# Espressylu-0_6.net
KiCad netlist of a schematic drawn in EAGLE
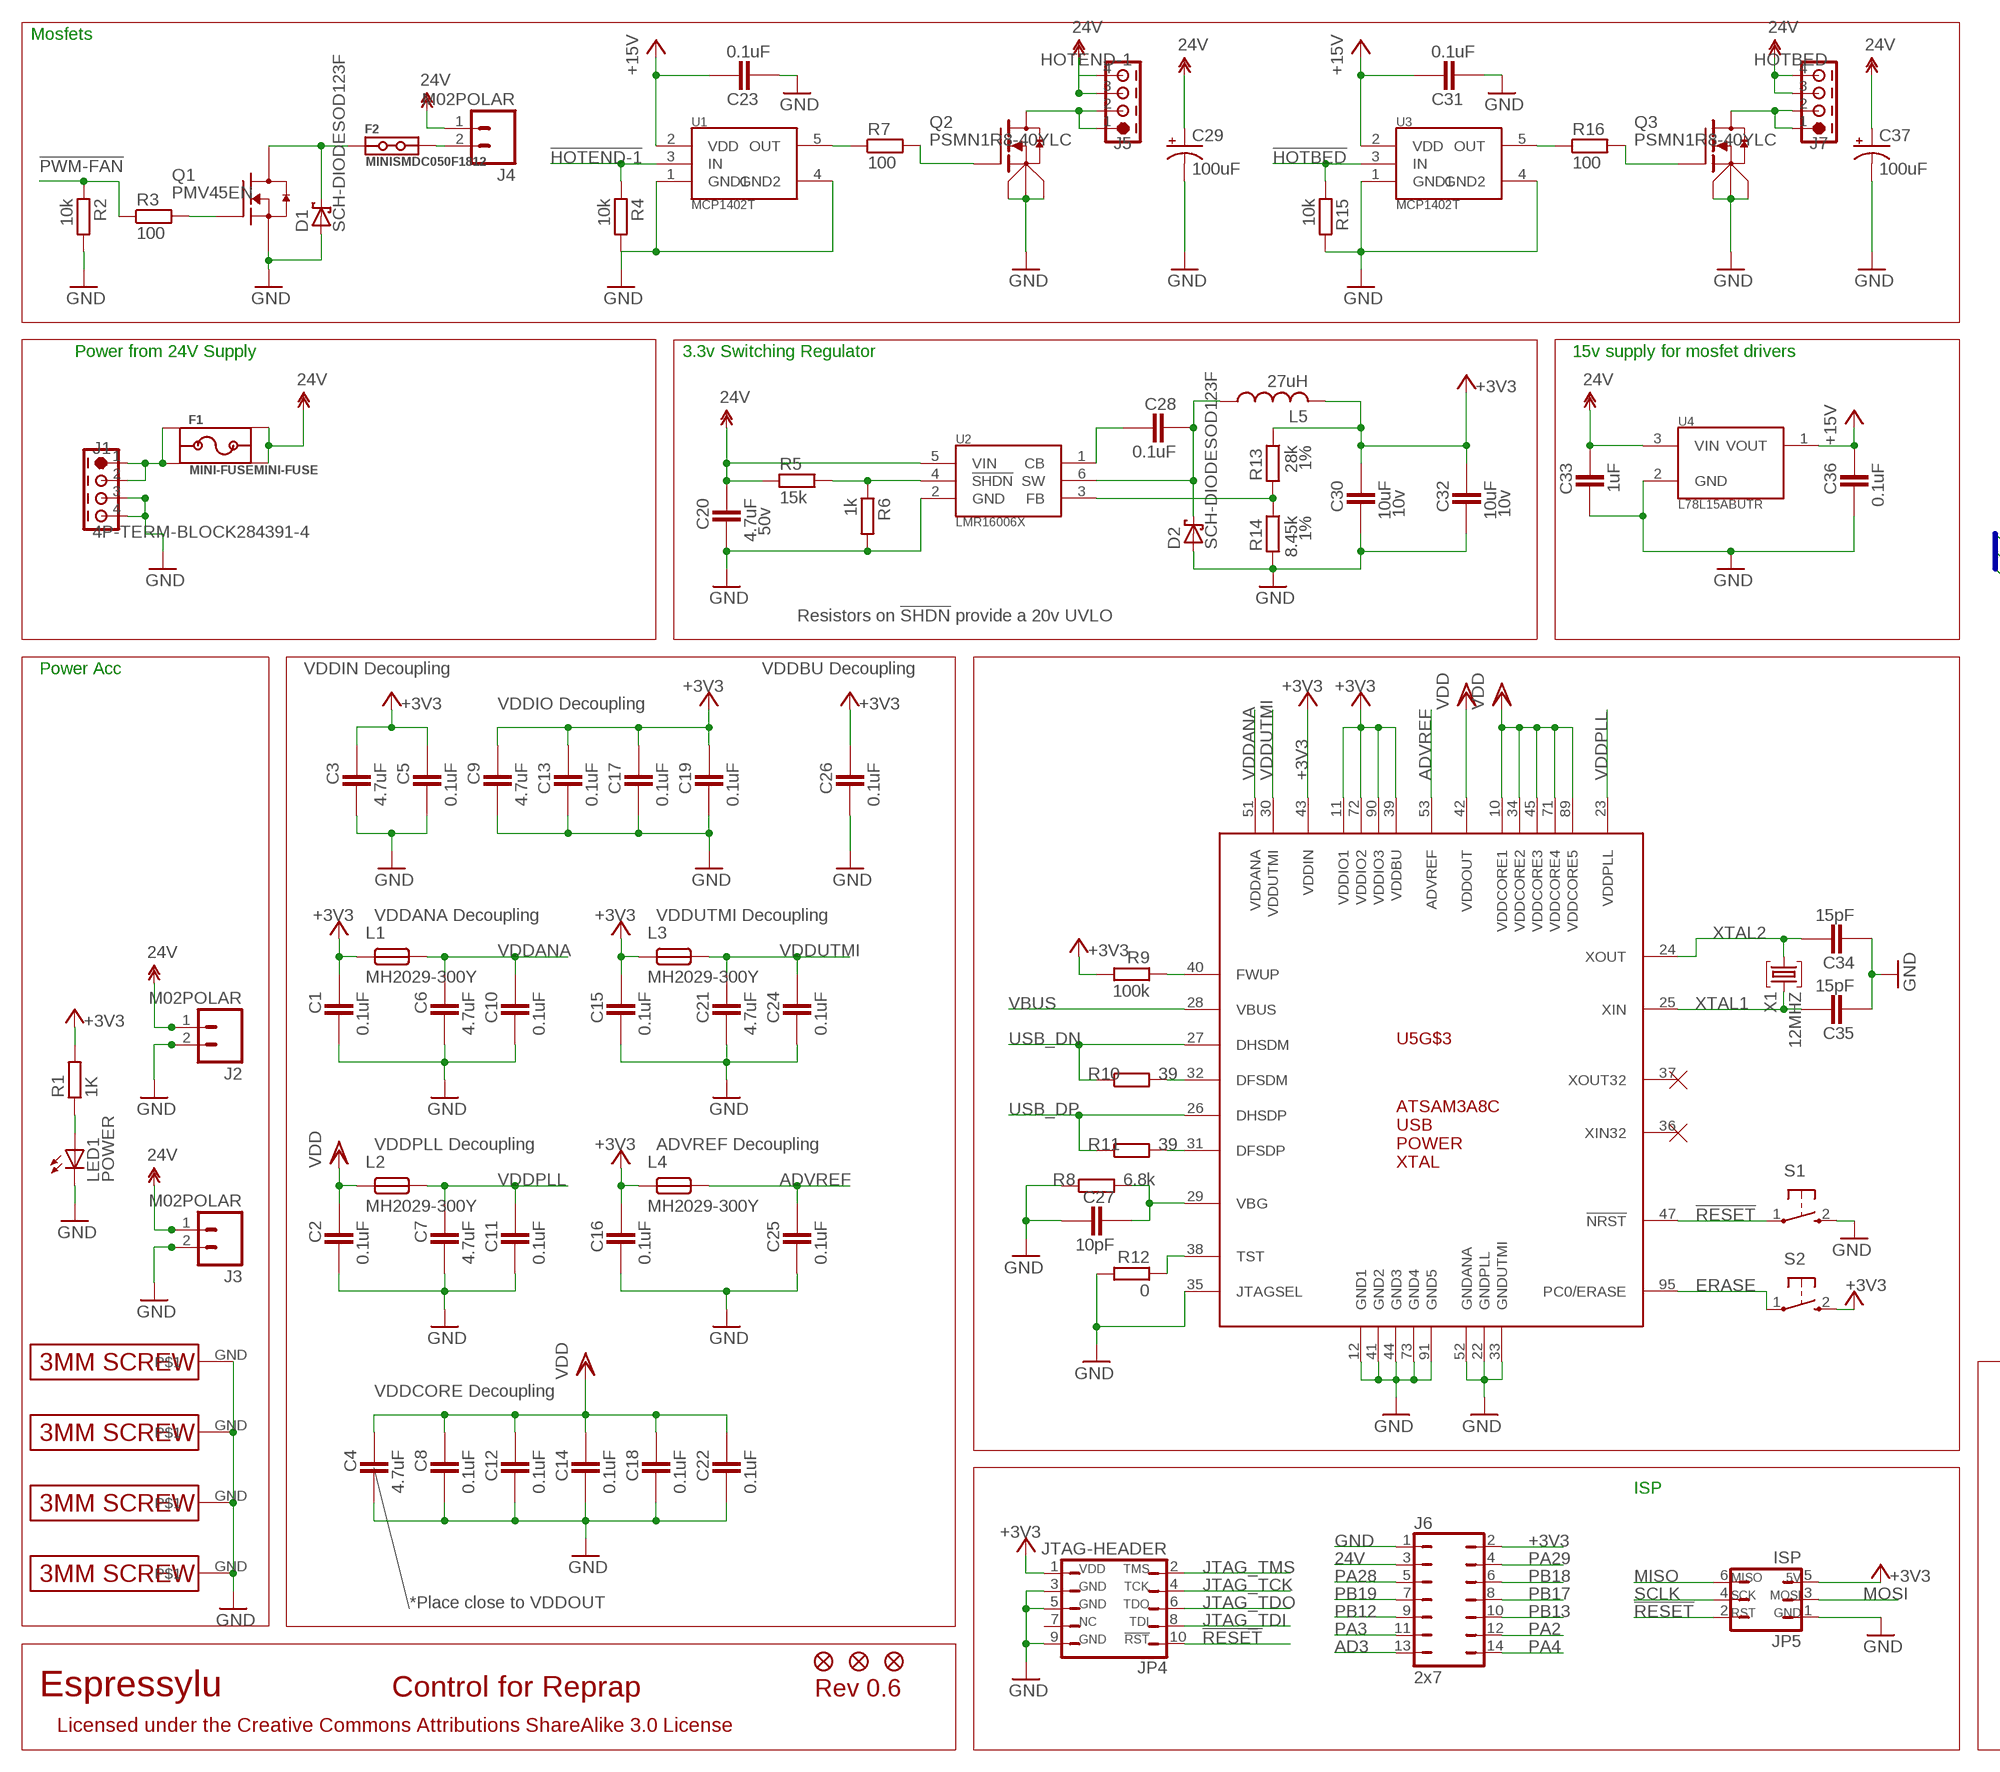
[diagram p0: schematic, sheet 1, part 1 of 2]
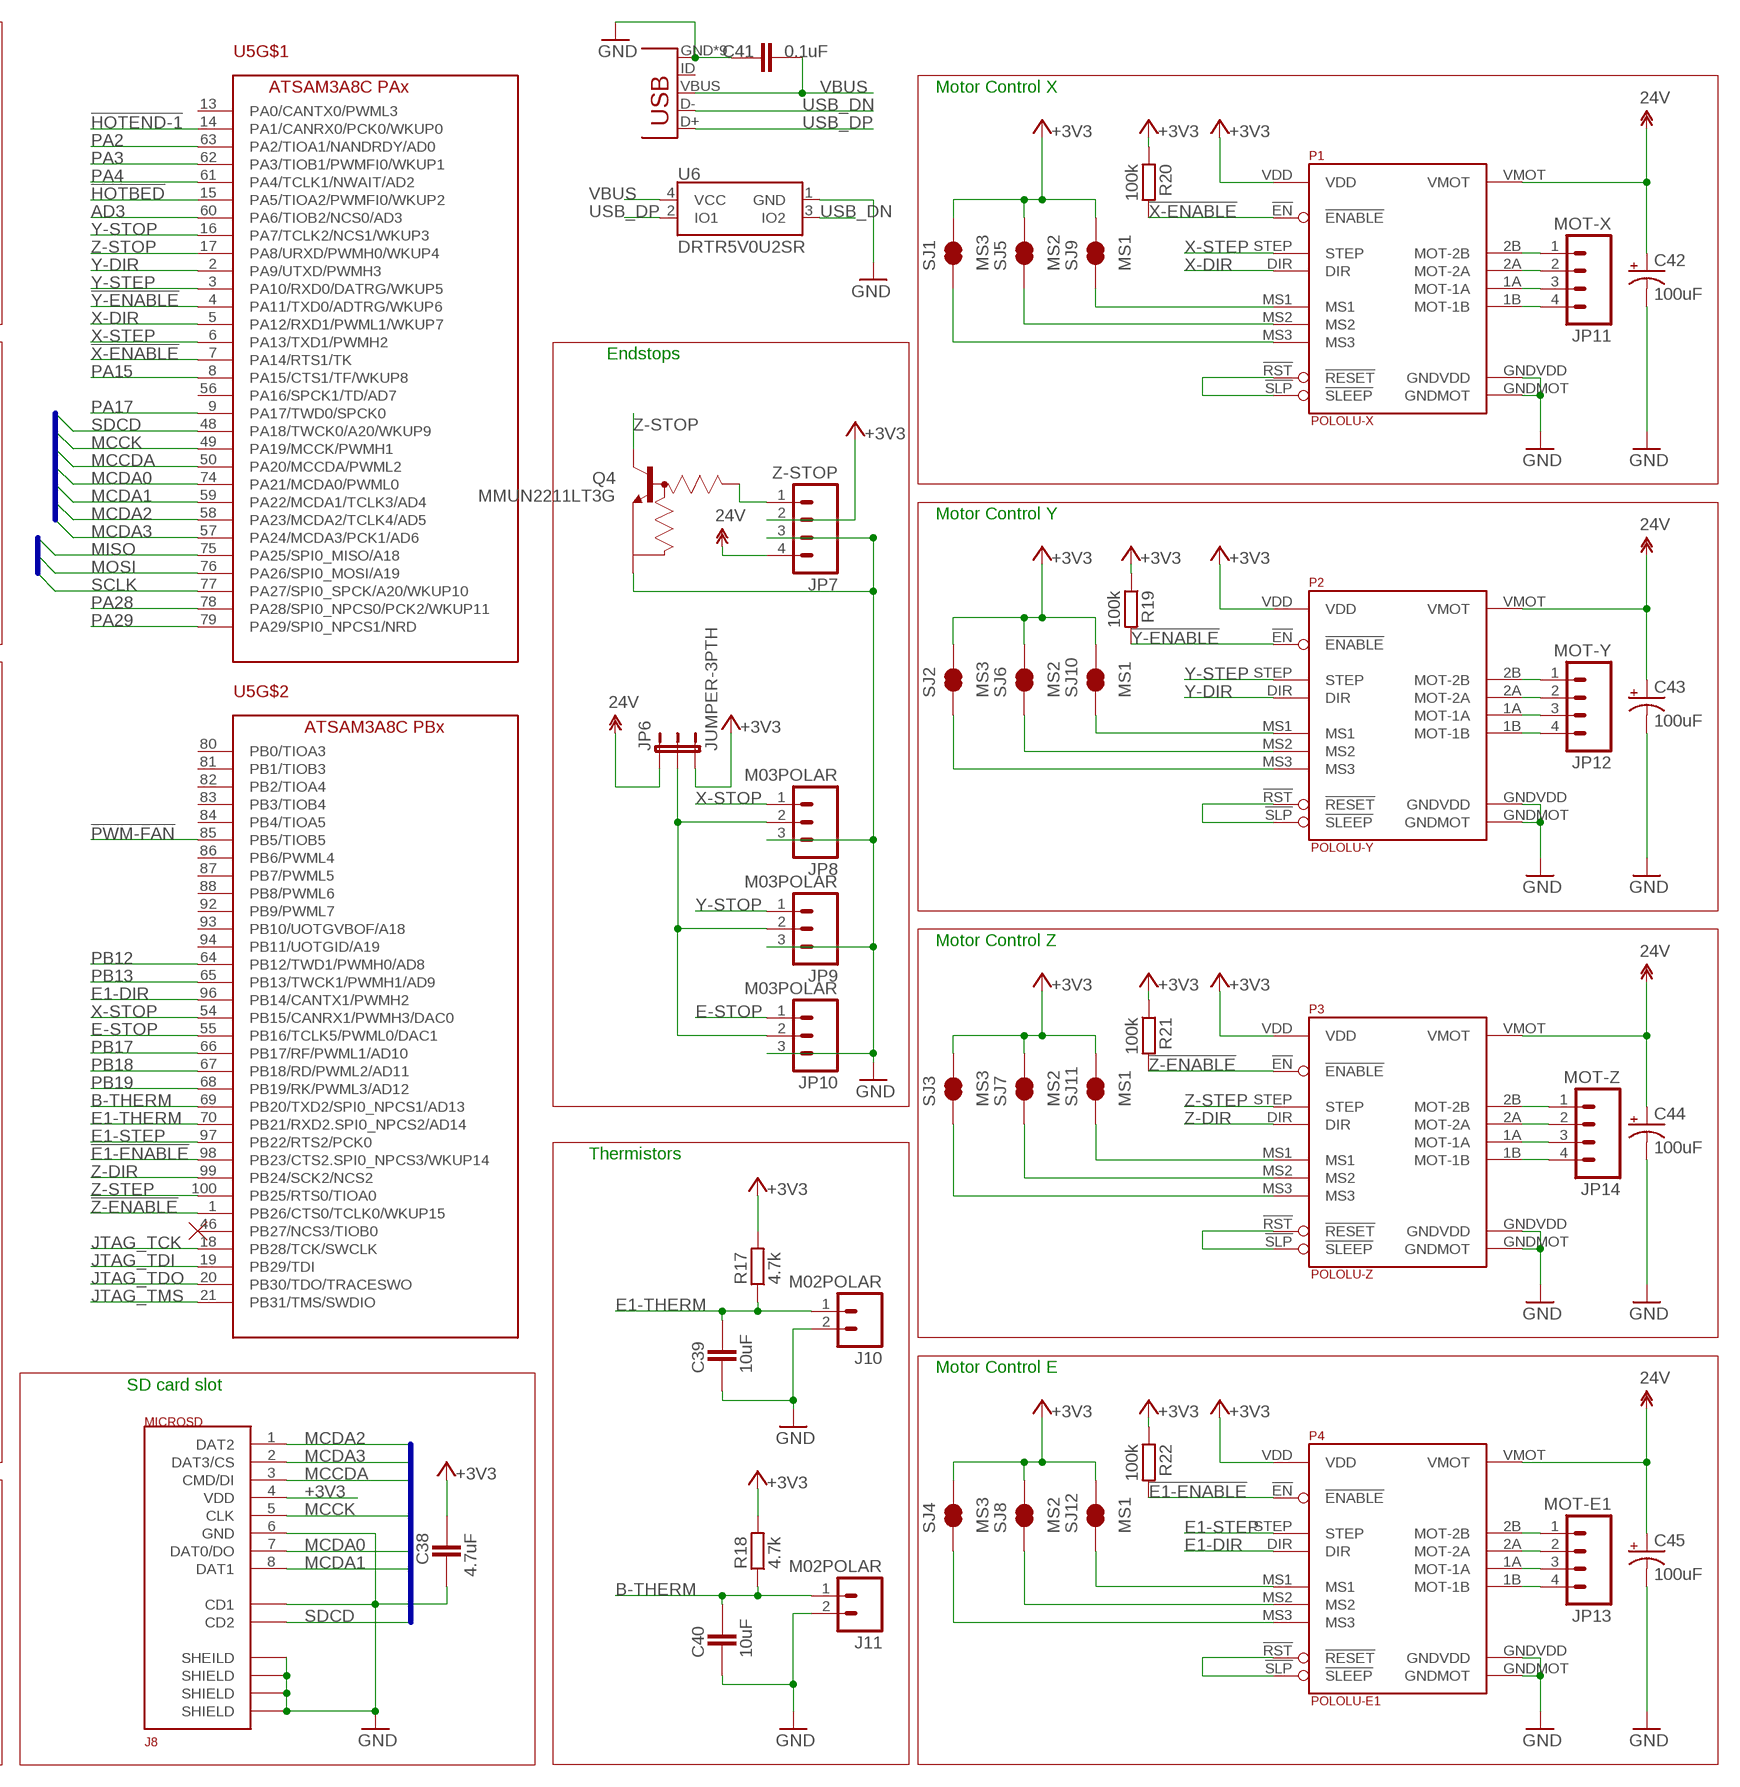
[diagram p1: schematic, sheet 1, part 2 of 2]

(export (version "E")
  (design (tool "Eeschema 10.0.6"))
  (components
    (comp (ref "C1")
      (value "0.1uF")
      (footprint "eagle-import:CAPC1005X60N")
      (fields
        (field (name "MANUFACTURER") "Samsung")
        (field (name "MANUFACTURER_PART_NUMBER") "CL05A104KQ5NNNC")
        (field (name "TOLERANCE") "10%")
      )
      (libsource (lib "eagle-import") (part "CAPACITOR_0402"))
    )
    (comp (ref "C2")
      (value "0.1uF")
      (footprint "eagle-import:CAPC1005X60N")
      (fields
        (field (name "MANUFACTURER") "Samsung")
        (field (name "MANUFACTURER_PART_NUMBER") "CL05A104KQ5NNNC")
        (field (name "TOLERANCE") "10%")
      )
      (libsource (lib "eagle-import") (part "CAPACITOR_0402"))
    )
    (comp (ref "C3")
      (value "4.7uF")
      (footprint "eagle-import:CAPC1608X92N")
      (fields
        (field (name "MANUFACTURER") "Samsung")
        (field (name "MANUFACTURER_PART_NUMBER") "CL10B475KQ8NQNC")
        (field (name "TOLERANCE") "10%")
        (field (name "VDC") "6.3V")
      )
      (libsource (lib "eagle-import") (part "CAPACITOR_0603"))
    )
    (comp (ref "C4")
      (value "4.7uF")
      (footprint "eagle-import:CAPC1608X92N")
      (fields
        (field (name "MANUFACTURER") "Samsung")
        (field (name "MANUFACTURER_PART_NUMBER") "CL10B475KQ8NQNC")
        (field (name "TOLERANCE") "10%")
        (field (name "VDC") "6.3V")
      )
      (libsource (lib "eagle-import") (part "CAPACITOR_0603"))
    )
    (comp (ref "C5")
      (value "0.1uF")
      (footprint "eagle-import:CAPC1005X60N")
      (fields
        (field (name "MANUFACTURER") "Samsung")
        (field (name "MANUFACTURER_PART_NUMBER") "CL05A104KQ5NNNC")
        (field (name "TOLERANCE") "10%")
      )
      (libsource (lib "eagle-import") (part "CAPACITOR_0402"))
    )
    (comp (ref "C6")
      (value "4.7uF")
      (footprint "eagle-import:CAPC1608X92N")
      (fields
        (field (name "MANUFACTURER") "Samsung")
        (field (name "MANUFACTURER_PART_NUMBER") "CL10B475KQ8NQNC")
        (field (name "TOLERANCE") "10%")
        (field (name "VDC") "6.3V")
      )
      (libsource (lib "eagle-import") (part "CAPACITOR_0603"))
    )
    (comp (ref "C7")
      (value "4.7uF")
      (footprint "eagle-import:CAPC1608X92N")
      (fields
        (field (name "MANUFACTURER") "Samsung")
        (field (name "MANUFACTURER_PART_NUMBER") "CL10B475KQ8NQNC")
        (field (name "TOLERANCE") "10%")
        (field (name "VDC") "6.3V")
      )
      (libsource (lib "eagle-import") (part "CAPACITOR_0603"))
    )
    (comp (ref "C8")
      (value "0.1uF")
      (footprint "eagle-import:CAPC1005X60N")
      (fields
        (field (name "MANUFACTURER") "Samsung")
        (field (name "MANUFACTURER_PART_NUMBER") "CL05A104KQ5NNNC")
        (field (name "TOLERANCE") "10%")
      )
      (libsource (lib "eagle-import") (part "CAPACITOR_0402"))
    )
    (comp (ref "C9")
      (value "4.7uF")
      (footprint "eagle-import:CAPC1608X92N")
      (fields
        (field (name "MANUFACTURER") "Samsung")
        (field (name "MANUFACTURER_PART_NUMBER") "CL10B475KQ8NQNC")
        (field (name "TOLERANCE") "10%")
        (field (name "VDC") "6.3V")
      )
      (libsource (lib "eagle-import") (part "CAPACITOR_0603"))
    )
    (comp (ref "C10")
      (value "0.1uF")
      (footprint "eagle-import:CAPC1005X60N")
      (fields
        (field (name "MANUFACTURER") "Samsung")
        (field (name "MANUFACTURER_PART_NUMBER") "CL05A104KQ5NNNC")
        (field (name "TOLERANCE") "10%")
      )
      (libsource (lib "eagle-import") (part "CAPACITOR_0402"))
    )
    (comp (ref "C11")
      (value "0.1uF")
      (footprint "eagle-import:CAPC1005X60N")
      (fields
        (field (name "MANUFACTURER") "Samsung")
        (field (name "MANUFACTURER_PART_NUMBER") "CL05A104KQ5NNNC")
        (field (name "TOLERANCE") "10%")
      )
      (libsource (lib "eagle-import") (part "CAPACITOR_0402"))
    )
    (comp (ref "C12")
      (value "0.1uF")
      (footprint "eagle-import:CAPC1005X60N")
      (fields
        (field (name "MANUFACTURER") "Samsung")
        (field (name "MANUFACTURER_PART_NUMBER") "CL05A104KQ5NNNC")
        (field (name "TOLERANCE") "10%")
      )
      (libsource (lib "eagle-import") (part "CAPACITOR_0402"))
    )
    (comp (ref "C13")
      (value "0.1uF")
      (footprint "eagle-import:CAPC1005X60N")
      (fields
        (field (name "MANUFACTURER") "Samsung")
        (field (name "MANUFACTURER_PART_NUMBER") "CL05A104KQ5NNNC")
        (field (name "TOLERANCE") "10%")
      )
      (libsource (lib "eagle-import") (part "CAPACITOR_0402"))
    )
    (comp (ref "C14")
      (value "0.1uF")
      (footprint "eagle-import:CAPC1005X60N")
      (fields
        (field (name "MANUFACTURER") "Samsung")
        (field (name "MANUFACTURER_PART_NUMBER") "CL05A104KQ5NNNC")
        (field (name "TOLERANCE") "10%")
      )
      (libsource (lib "eagle-import") (part "CAPACITOR_0402"))
    )
    (comp (ref "C15")
      (value "0.1uF")
      (footprint "eagle-import:CAPC1005X60N")
      (fields
        (field (name "MANUFACTURER") "Samsung")
        (field (name "MANUFACTURER_PART_NUMBER") "CL05A104KQ5NNNC")
        (field (name "TOLERANCE") "10%")
      )
      (libsource (lib "eagle-import") (part "CAPACITOR_0402"))
    )
    (comp (ref "C16")
      (value "0.1uF")
      (footprint "eagle-import:CAPC1005X60N")
      (fields
        (field (name "MANUFACTURER") "Samsung")
        (field (name "MANUFACTURER_PART_NUMBER") "CL05A104KQ5NNNC")
        (field (name "TOLERANCE") "10%")
      )
      (libsource (lib "eagle-import") (part "CAPACITOR_0402"))
    )
    (comp (ref "C17")
      (value "0.1uF")
      (footprint "eagle-import:CAPC1005X60N")
      (fields
        (field (name "MANUFACTURER") "Samsung")
        (field (name "MANUFACTURER_PART_NUMBER") "CL05A104KQ5NNNC")
        (field (name "TOLERANCE") "10%")
      )
      (libsource (lib "eagle-import") (part "CAPACITOR_0402"))
    )
    (comp (ref "C18")
      (value "0.1uF")
      (footprint "eagle-import:CAPC1005X60N")
      (fields
        (field (name "MANUFACTURER") "Samsung")
        (field (name "MANUFACTURER_PART_NUMBER") "CL05A104KQ5NNNC")
        (field (name "TOLERANCE") "10%")
      )
      (libsource (lib "eagle-import") (part "CAPACITOR_0402"))
    )
    (comp (ref "C19")
      (value "0.1uF")
      (footprint "eagle-import:CAPC1005X60N")
      (fields
        (field (name "MANUFACTURER") "Samsung")
        (field (name "MANUFACTURER_PART_NUMBER") "CL05A104KQ5NNNC")
        (field (name "TOLERANCE") "10%")
      )
      (libsource (lib "eagle-import") (part "CAPACITOR_0402"))
    )
    (comp (ref "C20")
      (value "4.7uF")
      (footprint "eagle-import:CAPC3215X168N")
      (fields
        (field (name "MANUFACTURER") "Yaiyo Yuden")
        (field (name "MANUFACTURER_PART_NUMBER") "UMK316AB7475KL-T")
        (field (name "TOLERANCE") "10%")
        (field (name "VDC") "50v")
      )
      (libsource (lib "eagle-import") (part "CAPACITOR_1206"))
    )
    (comp (ref "C21")
      (value "4.7uF")
      (footprint "eagle-import:CAPC1608X92N")
      (fields
        (field (name "MANUFACTURER") "Samsung")
        (field (name "MANUFACTURER_PART_NUMBER") "CL10B475KQ8NQNC")
        (field (name "TOLERANCE") "10%")
        (field (name "VDC") "6.3V")
      )
      (libsource (lib "eagle-import") (part "CAPACITOR_0603"))
    )
    (comp (ref "C22")
      (value "0.1uF")
      (footprint "eagle-import:CAPC1005X60N")
      (fields
        (field (name "MANUFACTURER") "Samsung")
        (field (name "MANUFACTURER_PART_NUMBER") "CL05A104KQ5NNNC")
        (field (name "TOLERANCE") "10%")
      )
      (libsource (lib "eagle-import") (part "CAPACITOR_0402"))
    )
    (comp (ref "C23")
      (value "0.1uF")
      (footprint "eagle-import:CAPC1005X60N")
      (fields (field (name "TOLERANCE") "20%"))
      (libsource (lib "eagle-import") (part "CAPACITOR_0402"))
    )
    (comp (ref "C24")
      (value "0.1uF")
      (footprint "eagle-import:CAPC1005X60N")
      (fields
        (field (name "MANUFACTURER") "Samsung")
        (field (name "MANUFACTURER_PART_NUMBER") "CL05A104KQ5NNNC")
        (field (name "TOLERANCE") "10%")
      )
      (libsource (lib "eagle-import") (part "CAPACITOR_0402"))
    )
    (comp (ref "C25")
      (value "0.1uF")
      (footprint "eagle-import:CAPC1005X60N")
      (fields
        (field (name "MANUFACTURER") "Samsung")
        (field (name "MANUFACTURER_PART_NUMBER") "CL05A104KQ5NNNC")
        (field (name "TOLERANCE") "10%")
      )
      (libsource (lib "eagle-import") (part "CAPACITOR_0402"))
    )
    (comp (ref "C26")
      (value "0.1uF")
      (footprint "eagle-import:CAPC1005X60N")
      (fields
        (field (name "MANUFACTURER") "Samsung")
        (field (name "MANUFACTURER_PART_NUMBER") "CL05A104KQ5NNNC")
        (field (name "TOLERANCE") "10%")
      )
      (libsource (lib "eagle-import") (part "CAPACITOR_0402"))
    )
    (comp (ref "C27")
      (value "10pF")
      (footprint "eagle-import:CAPC1005X60N")
      (fields
        (field (name "MANUFACTURER") "Samsung")
        (field (name "MANUFACTURER_PART_NUMBER") "CL10C100JB8NCNC")
        (field (name "TOLERANCE") "5%")
      )
      (libsource (lib "eagle-import") (part "CAPACITOR_0402"))
    )
    (comp (ref "C28")
      (value "0.1uF")
      (footprint "eagle-import:CAPC1005X60N")
      (fields
        (field (name "MANUFACTURER") "Samsung")
        (field (name "MANUFACTURER_PART_NUMBER") "CL10B104KB8NNNC")
        (field (name "TOLERANCE") "10%")
      )
      (libsource (lib "eagle-import") (part "CAPACITOR_0402"))
    )
    (comp (ref "C29")
      (value "100uF")
      (footprint "eagle-import:PANASONIC_D")
      (fields
        (field (name "MANUFACTURER") "Panasonic")
        (field (name "MANUFACTURER_PART_NUMBER") "EEE-FTH101XAP")
        (field (name "TOLERANCE") "20%")
      )
      (libsource (lib "eagle-import") (part "CPOL-USD"))
    )
    (comp (ref "C30")
      (value "10uF")
      (footprint "eagle-import:CAPC2012X145AN")
      (fields
        (field (name "MANUFACTURER") "Murata")
        (field (name "MANUFACTURER_PART_NUMBER") "GRM21BR71A106KE51L")
        (field (name "TOLERANCE") "10%")
        (field (name "VDC") "10v")
      )
      (libsource (lib "eagle-import") (part "CAPACITOR_0805"))
    )
    (comp (ref "C31")
      (value "0.1uF")
      (footprint "eagle-import:CAPC1005X60N")
      (fields (field (name "TOLERANCE") "20%"))
      (libsource (lib "eagle-import") (part "CAPACITOR_0402"))
    )
    (comp (ref "C32")
      (value "10uF")
      (footprint "eagle-import:CAPC2012X145AN")
      (fields
        (field (name "MANUFACTURER") "Murata")
        (field (name "MANUFACTURER_PART_NUMBER") "GRM21BR71A106KE51L")
        (field (name "TOLERANCE") "10%")
        (field (name "VDC") "10v")
      )
      (libsource (lib "eagle-import") (part "CAPACITOR_0805"))
    )
    (comp (ref "C33")
      (value "1uF")
      (footprint "eagle-import:CAPC1005X60N")
      (fields (field (name "TOLERANCE") "20%"))
      (libsource (lib "eagle-import") (part "CAPACITOR_0402"))
    )
    (comp (ref "C34")
      (value "15pF")
      (footprint "eagle-import:CAPC1005X60N")
      (fields
        (field (name "MANUFACTURER") "Samsung")
        (field (name "MANUFACTURER_PART_NUMBER") "CL05C150JB5NNNC")
        (field (name "TOLERANCE") "5%")
      )
      (libsource (lib "eagle-import") (part "CAPACITOR_0402"))
    )
    (comp (ref "C35")
      (value "15pF")
      (footprint "eagle-import:CAPC1005X60N")
      (fields
        (field (name "MANUFACTURER") "Samsung")
        (field (name "MANUFACTURER_PART_NUMBER") "CL05C150JB5NNNC")
        (field (name "TOLERANCE") "5%")
      )
      (libsource (lib "eagle-import") (part "CAPACITOR_0402"))
    )
    (comp (ref "C36")
      (value "0.1uF")
      (footprint "eagle-import:CAPC1005X60N")
      (fields (field (name "TOLERANCE") "20%"))
      (libsource (lib "eagle-import") (part "CAPACITOR_0402"))
    )
    (comp (ref "C37")
      (value "100uF")
      (footprint "eagle-import:PANASONIC_D")
      (fields
        (field (name "MANUFACTURER") "Panasonic")
        (field (name "MANUFACTURER_PART_NUMBER") "EEE-FTH101XAP")
        (field (name "TOLERANCE") "20%")
      )
      (libsource (lib "eagle-import") (part "CPOL-USD"))
    )
    (comp (ref "C38")
      (value "4.7uF")
      (footprint "eagle-import:CAPC1608X92N")
      (fields
        (field (name "MANUFACTURER") "Samsung")
        (field (name "MANUFACTURER_PART_NUMBER") "CL10B475KQ8NQNC")
        (field (name "TOLERANCE") "10%")
        (field (name "VDC") "6.3V")
      )
      (libsource (lib "eagle-import") (part "CAPACITOR_0603"))
    )
    (comp (ref "C39")
      (value "10uF")
      (footprint "eagle-import:CAPC1005X60N")
      (fields
        (field (name "MANUFACTURER") "Murata")
        (field (name "MANUFACTURER_PART_NUMBER") "GRM188R61C106MA73D")
        (field (name "TOLERANCE") "20%")
      )
      (libsource (lib "eagle-import") (part "CAPACITOR_0402"))
    )
    (comp (ref "C40")
      (value "10uF")
      (footprint "eagle-import:CAPC1005X60N")
      (fields
        (field (name "MANUFACTURER") "Murata")
        (field (name "MANUFACTURER_PART_NUMBER") "GRM188R61C106MA73D")
        (field (name "TOLERANCE") "20%")
      )
      (libsource (lib "eagle-import") (part "CAPACITOR_0402"))
    )
    (comp (ref "C41")
      (value "0.1uF")
      (footprint "eagle-import:CAPC1005X60N")
      (fields
        (field (name "MANUFACTURER") "Murata")
        (field (name "MANUFACTURER_PART_NUMBER") "GRM188R71C104KA01D")
        (field (name "TOLERANCE") "10%")
      )
      (libsource (lib "eagle-import") (part "CAPACITOR_0402"))
    )
    (comp (ref "C42")
      (value "100uF")
      (footprint "eagle-import:PANASONIC_D")
      (fields
        (field (name "MANUFACTURER") "Panasonic")
        (field (name "MANUFACTURER_PART_NUMBER") "EEE-FTH101XAP")
        (field (name "TOLERANCE") "20%")
      )
      (libsource (lib "eagle-import") (part "CPOL-USD"))
    )
    (comp (ref "C43")
      (value "100uF")
      (footprint "eagle-import:PANASONIC_D")
      (fields
        (field (name "MANUFACTURER") "Panasonic")
        (field (name "MANUFACTURER_PART_NUMBER") "EEE-FTH101XAP")
        (field (name "TOLERANCE") "20%")
      )
      (libsource (lib "eagle-import") (part "CPOL-USD"))
    )
    (comp (ref "C44")
      (value "100uF")
      (footprint "eagle-import:PANASONIC_D")
      (fields
        (field (name "MANUFACTURER") "Panasonic")
        (field (name "MANUFACTURER_PART_NUMBER") "EEE-FTH101XAP")
        (field (name "TOLERANCE") "20%")
      )
      (libsource (lib "eagle-import") (part "CPOL-USD"))
    )
    (comp (ref "C45")
      (value "100uF")
      (footprint "eagle-import:PANASONIC_D")
      (fields
        (field (name "MANUFACTURER") "Panasonic")
        (field (name "MANUFACTURER_PART_NUMBER") "EEE-FTH101XAP")
        (field (name "TOLERANCE") "20%")
      )
      (libsource (lib "eagle-import") (part "CPOL-USD"))
    )
    (comp (ref "D1")
      (value "SCH-DIODESOD123F")
      (footprint "eagle-import:SOD123F")
      (fields
        (field (name "MANUFACTURER") "NXP Semiconductors")
        (field (name "MANUFACTURER_PART_NUMBER") "PMEG4010CEH,115")
        (field (name "CURRENT") "1A")
        (field (name "MANUFACTURER_1") "NXP Semiconductors")
      )
      (libsource (lib "eagle-import") (part "SCH-DIODESOD123F"))
    )
    (comp (ref "D2")
      (value "SCH-DIODESOD123F")
      (footprint "eagle-import:SOD123F")
      (fields
        (field (name "MANUFACTURER") "NXP Semiconductors")
        (field (name "MANUFACTURER_PART_NUMBER") "PMEG4010CEH,115")
        (field (name "CURRENT") "1A")
        (field (name "MANUFACTURER_1") "NXP Semiconductors")
        (field (name "MANUFACTURER_PART_NUMBER_1") "PMEG4010CEH,115")
        (field (name "REVERSE_VOLTAGE") "40V")
      )
      (libsource (lib "eagle-import") (part "SCH-DIODESOD123F"))
    )
    (comp (ref "F1")
      (value "MINI-FUSEMINI-FUSE")
      (footprint "eagle-import:MINI_FUSE")
      (fields (field (name "MANUFACTURER") "Keystone") (field (name "MANUFACTURER_PART_NUMBER") "3568"))
      (libsource (lib "eagle-import") (part "MINI-FUSEMINI-FUSE"))
    )
    (comp (ref "F2")
      (value "MINISMDC050F1812")
      (footprint "eagle-import:MINISMDC")
      (fields
        (field (name "MANUFACTURER") "TE Connectivity")
        (field (name "MANUFACTURER_PART_NUMBER") "MINISMDC050F-2")
      )
      (libsource (lib "eagle-import") (part "MINISMDC050F1812"))
    )
    (comp (ref "J1")
      (value "4P-TERM-BLOCK284391-4")
      (footprint "eagle-import:284391-4")
      (fields
        (field (name "MANUFACTURER") "TE Connectivity")
        (field (name "MANUFACTURER_PART_NUMBER") "284391-4")
      )
      (libsource (lib "eagle-import") (part "4P-TERM-BLOCK284391-4"))
    )
    (comp (ref "J2")
      (value "M02POLAR")
      (footprint "eagle-import:MOLEX-1X2")
      (description "CONN HEADER 2POS .100 VERT TIN")
      (fields (field (name "MANUFACTURER") "Molex") (field (name "MANUFACTURER_PART_NUMBER") "0022272021"))
      (libsource (lib "eagle-import") (part "M02POLAR"))
    )
    (comp (ref "J3")
      (value "M02POLAR")
      (footprint "eagle-import:MOLEX-1X2")
      (description "CONN HEADER 2POS .100 VERT TIN")
      (fields (field (name "MANUFACTURER") "Molex") (field (name "MANUFACTURER_PART_NUMBER") "0022272021"))
      (libsource (lib "eagle-import") (part "M02POLAR"))
    )
    (comp (ref "J4")
      (value "M02POLAR")
      (footprint "eagle-import:MOLEX-1X2")
      (description "CONN HEADER 2POS .100 VERT TIN")
      (fields (field (name "MANUFACTURER") "Molex") (field (name "MANUFACTURER_PART_NUMBER") "0022272021"))
      (libsource (lib "eagle-import") (part "M02POLAR"))
    )
    (comp (ref "J5")
      (value "HOTEND-1")
      (footprint "eagle-import:284391-4")
      (fields
        (field (name "MANUFACTURER") "TE Connectivity")
        (field (name "MANUFACTURER_PART_NUMBER") "284391-4")
      )
      (libsource (lib "eagle-import") (part "4P-TERM-BLOCK284391-4"))
    )
    (comp (ref "J6")
      (value "2x7")
      (footprint "eagle-import:JP7Q")
      (description "DIL VERTICAL PC TAIL PIN HEADER")
      (fields (field (name "MANUFACTURER") "Harwin") (field (name "MANUFACTURER_PART_NUMBER") "M20-9980746"))
      (libsource (lib "eagle-import") (part "JP7Q"))
    )
    (comp (ref "J7")
      (value "HOTBED")
      (footprint "eagle-import:284391-4")
      (fields
        (field (name "MANUFACTURER") "TE Connectivity")
        (field (name "MANUFACTURER_PART_NUMBER") "284391-4")
      )
      (libsource (lib "eagle-import") (part "4P-TERM-BLOCK284391-4"))
    )
    (comp (ref "J8")
      (value "MICROSD")
      (footprint "eagle-import:AMPHENOL-MICROSD")
      (description "CONN MICRO SD CARD PUSH-PULL R/A")
      (fields
        (field (name "MANUFACTURER") "Amphenol")
        (field (name "MANUFACTURER_PART_NUMBER") "114-00841-68")
      )
      (libsource (lib "eagle-import") (part "MICROSD"))
    )
    (comp (ref "J9")
      (value "USB-MICRO-PTH")
      (footprint "eagle-import:USB-MICROB-PTH")
      (fields (field (name "MANUFACTURER") "FCI") (field (name "MANUFACTURER_PART_NUMBER") "10118194-0001LF"))
      (libsource (lib "eagle-import") (part "USB-MICRO-PTH"))
    )
    (comp (ref "J10")
      (value "M02POLAR")
      (footprint "eagle-import:MOLEX-1X2")
      (description "CONN HEADER 2POS .100 VERT TIN")
      (fields (field (name "MANUFACTURER") "Molex") (field (name "MANUFACTURER_PART_NUMBER") "0022272021"))
      (libsource (lib "eagle-import") (part "M02POLAR"))
    )
    (comp (ref "J11")
      (value "M02POLAR")
      (footprint "eagle-import:MOLEX-1X2")
      (description "CONN HEADER 2POS .100 VERT TIN")
      (fields (field (name "MANUFACTURER") "Molex") (field (name "MANUFACTURER_PART_NUMBER") "0022272021"))
      (libsource (lib "eagle-import") (part "M02POLAR"))
    )
    (comp (ref "JP1")
      (value "FIDUCIAL1X2.5")
      (footprint "eagle-import:FIDUCIAL-1X2.5")
      (libsource (lib "eagle-import") (part "FIDUCIAL1X2.5"))
    )
    (comp (ref "JP2")
      (value "FIDUCIAL1X2.5")
      (footprint "eagle-import:FIDUCIAL-1X2.5")
      (libsource (lib "eagle-import") (part "FIDUCIAL1X2.5"))
    )
    (comp (ref "JP3")
      (value "FIDUCIAL1X2.5")
      (footprint "eagle-import:FIDUCIAL-1X2.5")
      (libsource (lib "eagle-import") (part "FIDUCIAL1X2.5"))
    )
    (comp (ref "JP4")
      (value "JTAG-HEADER")
      (footprint "eagle-import:2X05-0.5-SMD")
      (fields
        (field (name "MANUFACTURER") "FCI")
        (field (name "MANUFACTURER_PART_NUMBER") "20021121-00010C4LF")
      )
      (libsource (lib "eagle-import") (part "JTAG-HEADER"))
    )
    (comp (ref "JP5")
      (value "ISP")
      (footprint "eagle-import:ISP")
      (libsource (lib "eagle-import") (part "PROGHEADER"))
    )
    (comp (ref "JP6")
      (value "JUMPER-3PTH")
      (footprint "eagle-import:1X03")
      (libsource (lib "eagle-import") (part "JUMPER-3PTH"))
    )
    (comp (ref "JP7")
      (value "Z-STOP")
      (footprint "eagle-import:MOLEX-1X4")
      (fields (field (name "MANUFACTURER") "Molex") (field (name "MANUFACTURER_PART_NUMBER") "0022272041"))
      (libsource (lib "eagle-import") (part "M04POLAR"))
    )
    (comp (ref "JP8")
      (value "M03POLAR")
      (footprint "eagle-import:MOLEX-1X3")
      (description "CONN HEADER 3POS .100 VERT TIN")
      (fields (field (name "MANUFACTURER") "Molex") (field (name "MANUFACTURER_PART_NUMBER") "0022272031"))
      (libsource (lib "eagle-import") (part "M03POLAR"))
    )
    (comp (ref "JP9")
      (value "M03POLAR")
      (footprint "eagle-import:MOLEX-1X3")
      (description "CONN HEADER 3POS .100 VERT TIN")
      (fields (field (name "MANUFACTURER") "Molex") (field (name "MANUFACTURER_PART_NUMBER") "0022272031"))
      (libsource (lib "eagle-import") (part "M03POLAR"))
    )
    (comp (ref "JP10")
      (value "M03POLAR")
      (footprint "eagle-import:MOLEX-1X3")
      (description "CONN HEADER 3POS .100 VERT TIN")
      (fields (field (name "MANUFACTURER") "Molex") (field (name "MANUFACTURER_PART_NUMBER") "0022272031"))
      (libsource (lib "eagle-import") (part "M03POLAR"))
    )
    (comp (ref "JP11")
      (value "MOT-X")
      (footprint "eagle-import:MOLEX-1X4")
      (fields (field (name "MANUFACTURER") "Molex") (field (name "MANUFACTURER_PART_NUMBER") "0022272041"))
      (libsource (lib "eagle-import") (part "M04POLAR"))
    )
    (comp (ref "JP12")
      (value "MOT-Y")
      (footprint "eagle-import:MOLEX-1X4")
      (fields (field (name "MANUFACTURER") "Molex") (field (name "MANUFACTURER_PART_NUMBER") "0022272041"))
      (libsource (lib "eagle-import") (part "M04POLAR"))
    )
    (comp (ref "JP13")
      (value "MOT-E1")
      (footprint "eagle-import:MOLEX-1X4")
      (fields (field (name "MANUFACTURER") "Molex") (field (name "MANUFACTURER_PART_NUMBER") "0022272041"))
      (libsource (lib "eagle-import") (part "M04POLAR"))
    )
    (comp (ref "JP14")
      (value "MOT-Z")
      (footprint "eagle-import:MOLEX-1X4")
      (fields (field (name "MANUFACTURER") "Molex") (field (name "MANUFACTURER_PART_NUMBER") "0022272041"))
      (libsource (lib "eagle-import") (part "M04POLAR"))
    )
    (comp (ref "L1")
      (value "MH2029-300Y")
      (footprint "eagle-import:FERRITE_BEAD_0805")
      (description "30 Ohm @ 100MHz")
      (fields (field (name "MANUFACTURER") "Bourns Inc"))
      (libsource (lib "eagle-import") (part "FERRITE_BEAD_0805"))
    )
    (comp (ref "L2")
      (value "MH2029-300Y")
      (footprint "eagle-import:FERRITE_BEAD_0805")
      (description "30 Ohm @ 100MHz")
      (fields (field (name "MANUFACTURER") "Bourns Inc"))
      (libsource (lib "eagle-import") (part "FERRITE_BEAD_0805"))
    )
    (comp (ref "L3")
      (value "MH2029-300Y")
      (footprint "eagle-import:FERRITE_BEAD_0805")
      (description "30 Ohm @ 100MHz")
      (fields (field (name "MANUFACTURER") "Bourns Inc"))
      (libsource (lib "eagle-import") (part "FERRITE_BEAD_0805"))
    )
    (comp (ref "L4")
      (value "MH2029-300Y")
      (footprint "eagle-import:FERRITE_BEAD_0805")
      (description "30 Ohm @ 100MHz")
      (fields (field (name "MANUFACTURER") "Bourns Inc"))
      (libsource (lib "eagle-import") (part "FERRITE_BEAD_0805"))
    )
    (comp (ref "L5")
      (value "27uH")
      (footprint "eagle-import:SDR0604")
      (fields
        (field (name "MANUFACTURER") "Bourns")
        (field (name "MANUFACTURER_1") "Bourns")
        (field (name "MANUFACTURER_PART_NUMBER") "SDR0604-270YL")
      )
      (libsource (lib "eagle-import") (part "INDUCTORSDR0604"))
    )
    (comp (ref "LED1")
      (value "POWER")
      (footprint "eagle-import:CHIPLED_0805")
      (fields
        (field (name "MANUFACTURER") "Kingbright")
        (field (name "MANUFACTURER_PART_NUMBER") "APT2012SGC")
      )
      (libsource (lib "eagle-import") (part "LEDCHIPLED_0805"))
    )
    (comp (ref "P1")
      (value "POLOLU-X")
      (footprint "eagle-import:POLOLU-STEPPER-PTH")
      (libsource (lib "eagle-import") (part "POLOLU-ALLEGRO"))
    )
    (comp (ref "P2")
      (value "POLOLU-Y")
      (footprint "eagle-import:POLOLU-STEPPER-PTH")
      (libsource (lib "eagle-import") (part "POLOLU-ALLEGRO"))
    )
    (comp (ref "P3")
      (value "POLOLU-Z")
      (footprint "eagle-import:POLOLU-STEPPER-PTH")
      (libsource (lib "eagle-import") (part "POLOLU-ALLEGRO"))
    )
    (comp (ref "P4")
      (value "POLOLU-E1")
      (footprint "eagle-import:POLOLU-STEPPER-PTH")
      (libsource (lib "eagle-import") (part "POLOLU-ALLEGRO"))
    )
    (comp (ref "Q1")
      (value "PMV45EN")
      (footprint "eagle-import:SOT23C")
      (fields
        (field (name "MANUFACTURER") "International Rectifier")
        (field (name "MANUFACTURER_PART_NUMBER") "IRLML2060TRPBF")
        (field (name "VOLTAGE") "60V")
      )
      (libsource (lib "eagle-import") (part "MOSFET-NCH_SOT-23"))
    )
    (comp (ref "Q2")
      (value "PSMN1R8-40YLC")
      (footprint "eagle-import:LFPACK-POWERPAK-SO8")
      (fields
        (field (name "MANUFACTURER") "NXP Semiconductors")
        (field (name "MANUFACTURER_PART_NUMBER") "PSMN1R8-40YLC,115")
        (field (name "VOLTAGE") "40V")
      )
      (libsource (lib "eagle-import") (part "PSMN1R8-40YLCPOWERPACK-S08"))
    )
    (comp (ref "Q3")
      (value "PSMN1R8-40YLC")
      (footprint "eagle-import:LFPACK-POWERPAK-SO8")
      (fields
        (field (name "MANUFACTURER") "NXP Semiconductors")
        (field (name "MANUFACTURER_PART_NUMBER") "PSMN1R8-40YLC,115")
        (field (name "VOLTAGE") "40V")
      )
      (libsource (lib "eagle-import") (part "PSMN1R8-40YLCPOWERPACK-S08"))
    )
    (comp (ref "Q4")
      (value "MMUN2211LT3G")
      (footprint "eagle-import:SOT23C")
      (description "TRANS PREBIAS NPN 246MW SOT23-3")
      (fields (field (name "MANUFACTURER") "ON Semiconductor"))
      (libsource (lib "eagle-import") (part "TRANSISTOR_NPN_BIASSOT23C"))
    )
    (comp (ref "R1")
      (value "1K")
      (footprint "eagle-import:RESC1608X55N")
      (libsource (lib "eagle-import") (part "RESISTOR_0603"))
    )
    (comp (ref "R2")
      (value "10k")
      (footprint "eagle-import:RESC1005X40AN")
      (libsource (lib "eagle-import") (part "RESISTOR_0402"))
    )
    (comp (ref "R3")
      (value "100")
      (footprint "eagle-import:RESC1005X40AN")
      (libsource (lib "eagle-import") (part "RESISTOR_0402"))
    )
    (comp (ref "R4")
      (value "10k")
      (footprint "eagle-import:RESC1005X40AN")
      (libsource (lib "eagle-import") (part "RESISTOR_0402"))
    )
    (comp (ref "R5")
      (value "15k")
      (footprint "eagle-import:RESC1005X40AN")
      (libsource (lib "eagle-import") (part "RESISTOR_0402"))
    )
    (comp (ref "R6")
      (value "1k")
      (footprint "eagle-import:RESC1005X40AN")
      (libsource (lib "eagle-import") (part "RESISTOR_0402"))
    )
    (comp (ref "R7")
      (value "100")
      (footprint "eagle-import:RESC1005X40AN")
      (libsource (lib "eagle-import") (part "RESISTOR_0402"))
    )
    (comp (ref "R8")
      (value "6.8k")
      (footprint "eagle-import:RESC1005X40AN")
      (fields (field (name "TOLERANCE") "1%"))
      (libsource (lib "eagle-import") (part "RESISTOR_0402"))
    )
    (comp (ref "R9")
      (value "100k")
      (footprint "eagle-import:RESC1005X40AN")
      (libsource (lib "eagle-import") (part "RESISTOR_0402"))
    )
    (comp (ref "R10")
      (value "39")
      (footprint "eagle-import:RESC1005X40AN")
      (fields (field (name "TOLERANCE") "1%"))
      (libsource (lib "eagle-import") (part "RESISTOR_0402"))
    )
    (comp (ref "R11")
      (value "39")
      (footprint "eagle-import:RESC1005X40AN")
      (fields (field (name "TOLERANCE") "1%"))
      (libsource (lib "eagle-import") (part "RESISTOR_0402"))
    )
    (comp (ref "R12")
      (value "0")
      (footprint "eagle-import:RESC1005X40AN")
      (libsource (lib "eagle-import") (part "RESISTOR_0402"))
    )
    (comp (ref "R13")
      (value "28k")
      (footprint "eagle-import:RESC1005X40AN")
      (fields (field (name "TOLERANCE") "1%"))
      (libsource (lib "eagle-import") (part "RESISTOR_0402"))
    )
    (comp (ref "R14")
      (value "8.45k")
      (footprint "eagle-import:RESC1005X40AN")
      (fields (field (name "TOLERANCE") "1%"))
      (libsource (lib "eagle-import") (part "RESISTOR_0402"))
    )
    (comp (ref "R15")
      (value "10k")
      (footprint "eagle-import:RESC1005X40AN")
      (libsource (lib "eagle-import") (part "RESISTOR_0402"))
    )
    (comp (ref "R16")
      (value "100")
      (footprint "eagle-import:RESC1005X40AN")
      (libsource (lib "eagle-import") (part "RESISTOR_0402"))
    )
    (comp (ref "R17")
      (value "4.7k")
      (footprint "eagle-import:RESC1005X40AN")
      (libsource (lib "eagle-import") (part "RESISTOR_0402"))
    )
    (comp (ref "R18")
      (value "4.7k")
      (footprint "eagle-import:RESC1005X40AN")
      (libsource (lib "eagle-import") (part "RESISTOR_0402"))
    )
    (comp (ref "R19")
      (value "100k")
      (footprint "eagle-import:RESC1005X40AN")
      (libsource (lib "eagle-import") (part "RESISTOR_0402"))
    )
    (comp (ref "R20")
      (value "100k")
      (footprint "eagle-import:RESC1005X40AN")
      (libsource (lib "eagle-import") (part "RESISTOR_0402"))
    )
    (comp (ref "R21")
      (value "100k")
      (footprint "eagle-import:RESC1005X40AN")
      (libsource (lib "eagle-import") (part "RESISTOR_0402"))
    )
    (comp (ref "R22")
      (value "100k")
      (footprint "eagle-import:RESC1005X40AN")
      (libsource (lib "eagle-import") (part "RESISTOR_0402"))
    )
    (comp (ref "S1")
      (value "TAC_SWITCH_2P-SMD")
      (footprint "eagle-import:TACTILE_SWITCH_2P_SMD")
      (fields
        (field (name "MANUFACTURER") "TE Connectivity")
        (field (name "MANUFACTURER_PART_NUMBER") "147873-2")
      )
      (libsource (lib "eagle-import") (part "TAC_SWITCH_2P-SMD"))
    )
    (comp (ref "S2")
      (value "TAC_SWITCH_2P-SMD")
      (footprint "eagle-import:TACTILE_SWITCH_2P_SMD")
      (fields
        (field (name "MANUFACTURER") "TE Connectivity")
        (field (name "MANUFACTURER_PART_NUMBER") "147873-2")
      )
      (libsource (lib "eagle-import") (part "TAC_SWITCH_2P-SMD"))
    )
    (comp (ref "SCREW1")
      (value "3MM-SCREW")
      (footprint "eagle-import:PLATEDSCREW")
      (libsource (lib "eagle-import") (part "3MM-SCREW"))
    )
    (comp (ref "SCREW2")
      (value "3MM-SCREW")
      (footprint "eagle-import:PLATEDSCREW")
      (libsource (lib "eagle-import") (part "3MM-SCREW"))
    )
    (comp (ref "SCREW3")
      (value "3MM-SCREW")
      (footprint "eagle-import:PLATEDSCREW")
      (libsource (lib "eagle-import") (part "3MM-SCREW"))
    )
    (comp (ref "SCREW4")
      (value "3MM-SCREW")
      (footprint "eagle-import:PLATEDSCREW")
      (libsource (lib "eagle-import") (part "3MM-SCREW"))
    )
    (comp (ref "SJ1")
      (value "MS3")
      (footprint "eagle-import:SJ_2S-TRACE")
      (libsource (lib "eagle-import") (part "SOLDERJUMPER-NCSJ-TRACE"))
    )
    (comp (ref "SJ2")
      (value "MS3")
      (footprint "eagle-import:SJ_2S-TRACE")
      (libsource (lib "eagle-import") (part "SOLDERJUMPER-NCSJ-TRACE"))
    )
    (comp (ref "SJ3")
      (value "MS3")
      (footprint "eagle-import:SJ_2S-TRACE")
      (libsource (lib "eagle-import") (part "SOLDERJUMPER-NCSJ-TRACE"))
    )
    (comp (ref "SJ4")
      (value "MS3")
      (footprint "eagle-import:SJ_2S-TRACE")
      (libsource (lib "eagle-import") (part "SOLDERJUMPER-NCSJ-TRACE"))
    )
    (comp (ref "SJ5")
      (value "MS2")
      (footprint "eagle-import:SJ_2S-TRACE")
      (libsource (lib "eagle-import") (part "SOLDERJUMPER-NCSJ-TRACE"))
    )
    (comp (ref "SJ6")
      (value "MS2")
      (footprint "eagle-import:SJ_2S-TRACE")
      (libsource (lib "eagle-import") (part "SOLDERJUMPER-NCSJ-TRACE"))
    )
    (comp (ref "SJ7")
      (value "MS2")
      (footprint "eagle-import:SJ_2S-TRACE")
      (libsource (lib "eagle-import") (part "SOLDERJUMPER-NCSJ-TRACE"))
    )
    (comp (ref "SJ8")
      (value "MS2")
      (footprint "eagle-import:SJ_2S-TRACE")
      (libsource (lib "eagle-import") (part "SOLDERJUMPER-NCSJ-TRACE"))
    )
    (comp (ref "SJ9")
      (value "MS1")
      (footprint "eagle-import:SJ_2S-TRACE")
      (libsource (lib "eagle-import") (part "SOLDERJUMPER-NCSJ-TRACE"))
    )
    (comp (ref "SJ10")
      (value "MS1")
      (footprint "eagle-import:SJ_2S-TRACE")
      (libsource (lib "eagle-import") (part "SOLDERJUMPER-NCSJ-TRACE"))
    )
    (comp (ref "SJ11")
      (value "MS1")
      (footprint "eagle-import:SJ_2S-TRACE")
      (libsource (lib "eagle-import") (part "SOLDERJUMPER-NCSJ-TRACE"))
    )
    (comp (ref "SJ12")
      (value "MS1")
      (footprint "eagle-import:SJ_2S-TRACE")
      (libsource (lib "eagle-import") (part "SOLDERJUMPER-NCSJ-TRACE"))
    )
    (comp (ref "U1")
      (value "MCP1402T")
      (footprint "eagle-import:SOT23-5")
      (fields
        (field (name "MANUFACTURER") "Microchip")
        (field (name "MANUFACTURER_PART_NUMBER") "MCP1402T-E/OT")
      )
      (libsource (lib "eagle-import") (part "MCP1402T"))
    )
    (comp (ref "U2")
      (value "LMR16006X")
      (footprint "eagle-import:TSOT6")
      (fields
        (field (name "MANUFACTURER") "Texas Instruments")
        (field (name "MANUFACTURER_PART_NUMBER") "LMR16006XDDCT")
      )
      (libsource (lib "eagle-import") (part "LMR16006X"))
    )
    (comp (ref "U3")
      (value "MCP1402T")
      (footprint "eagle-import:SOT23-5")
      (fields
        (field (name "MANUFACTURER") "Microchip")
        (field (name "MANUFACTURER_PART_NUMBER") "MCP1402T-E/OT")
      )
      (libsource (lib "eagle-import") (part "MCP1402T"))
    )
    (comp (ref "U4")
      (value "L78L15ABUTR")
      (footprint "eagle-import:SOT89")
      (fields (field (name "MANUFACTURER") "STMicroelectronics"))
      (libsource (lib "eagle-import") (part "L78L15ABUTR"))
    )
    (comp (ref "U5")
      (value "ATSAM3A8C-LQFP100")
      (footprint "eagle-import:LQFP100")
      (fields (field (name "MANUFACTURER") "Atmel") (field (name "MANUFACTURER_PART_NUMBER") "ATSAM3A8C"))
      (libsource (lib "eagle-import") (part "ATSAM3A8C-LQFP100"))
    )
    (comp (ref "U6")
      (value "DRTR5V0U2SR")
      (footprint "eagle-import:SOT143-R")
      (fields
        (field (name "MANUFACTURER") "Diodes Incorporated")
        (field (name "MANUFACTURER_PART_NUMBER") "DTR5V0U2SR")
      )
      (libsource (lib "eagle-import") (part "DRTR5V0U2SR"))
    )
    (comp (ref "X1")
      (value "12MHZ")
      (footprint "eagle-import:NDK-XTAL")
      (fields
        (field (name "MANUFACTURER") "Abracon LLC")
        (field (name "MANUFACTURER_PART_NUMBER") "ABM3-12.000MHZ-B2-T")
      )
      (libsource (lib "eagle-import") (part "XTAL"))
    )
  )
  (nets
    (net (code "1") (name "+3V3") (class "Default")
      (node (ref "C1") (pin "1") (pinfunction "1_1") (pintype "passive"))
      (node (ref "C13") (pin "1") (pinfunction "1_1") (pintype "passive"))
      (node (ref "C15") (pin "1") (pinfunction "1_1") (pintype "passive"))
      (node (ref "C16") (pin "1") (pinfunction "1_1") (pintype "passive"))
      (node (ref "C17") (pin "1") (pinfunction "1_1") (pintype "passive"))
      (node (ref "C19") (pin "1") (pinfunction "1_1") (pintype "passive"))
      (node (ref "C26") (pin "1") (pinfunction "1_1") (pintype "passive"))
      (node (ref "C3") (pin "1") (pinfunction "1_1") (pintype "passive"))
      (node (ref "C30") (pin "1") (pinfunction "1_1") (pintype "passive"))
      (node (ref "C32") (pin "1") (pinfunction "1_1") (pintype "passive"))
      (node (ref "C38") (pin "1") (pinfunction "1_1") (pintype "passive"))
      (node (ref "C5") (pin "1") (pinfunction "1_1") (pintype "passive"))
      (node (ref "C9") (pin "1") (pinfunction "1_1") (pintype "passive"))
      (node (ref "J6") (pin "2") (pinfunction "2_2") (pintype "passive"))
      (node (ref "J8") (pin "4") (pinfunction "VDD_4") (pintype "power_in"))
      (node (ref "JP4") (pin "1") (pinfunction "1_1") (pintype "passive"))
      (node (ref "JP5") (pin "5") (pinfunction "5_5") (pintype "passive"))
      (node (ref "JP6") (pin "3") (pinfunction "3_3") (pintype "passive"))
      (node (ref "JP7") (pin "2") (pinfunction "2_2") (pintype "passive"))
      (node (ref "L1") (pin "1") (pinfunction "1_1") (pintype "passive"))
      (node (ref "L3") (pin "1") (pinfunction "1_1") (pintype "passive"))
      (node (ref "L4") (pin "1") (pinfunction "1_1") (pintype "passive"))
      (node (ref "L5") (pin "2") (pinfunction "2_2") (pintype "passive"))
      (node (ref "P1") (pin "VDD") (pinfunction "VDD_VDD") (pintype "power_in"))
      (node (ref "P2") (pin "VDD") (pinfunction "VDD_VDD") (pintype "power_in"))
      (node (ref "P3") (pin "VDD") (pinfunction "VDD_VDD") (pintype "power_in"))
      (node (ref "P4") (pin "VDD") (pinfunction "VDD_VDD") (pintype "power_in"))
      (node (ref "R1") (pin "2") (pinfunction "2_2") (pintype "passive"))
      (node (ref "R13") (pin "1") (pinfunction "1_1") (pintype "passive"))
      (node (ref "R17") (pin "2") (pinfunction "2_2") (pintype "passive"))
      (node (ref "R18") (pin "2") (pinfunction "2_2") (pintype "passive"))
      (node (ref "R19") (pin "1") (pinfunction "1_1") (pintype "passive"))
      (node (ref "R20") (pin "1") (pinfunction "1_1") (pintype "passive"))
      (node (ref "R21") (pin "1") (pinfunction "1_1") (pintype "passive"))
      (node (ref "R22") (pin "1") (pinfunction "1_1") (pintype "passive"))
      (node (ref "R9") (pin "2") (pinfunction "2_2") (pintype "passive"))
      (node (ref "S2") (pin "2") (pinfunction "2_2") (pintype "passive"))
      (node (ref "SJ1") (pin "2") (pinfunction "2_2") (pintype "passive"))
      (node (ref "SJ10") (pin "2") (pinfunction "2_2") (pintype "passive"))
      (node (ref "SJ11") (pin "2") (pinfunction "2_2") (pintype "passive"))
      (node (ref "SJ12") (pin "2") (pinfunction "2_2") (pintype "passive"))
      (node (ref "SJ2") (pin "2") (pinfunction "2_2") (pintype "passive"))
      (node (ref "SJ3") (pin "2") (pinfunction "2_2") (pintype "passive"))
      (node (ref "SJ4") (pin "2") (pinfunction "2_2") (pintype "passive"))
      (node (ref "SJ5") (pin "2") (pinfunction "2_2") (pintype "passive"))
      (node (ref "SJ6") (pin "2") (pinfunction "2_2") (pintype "passive"))
      (node (ref "SJ7") (pin "2") (pinfunction "2_2") (pintype "passive"))
      (node (ref "SJ8") (pin "2") (pinfunction "2_2") (pintype "passive"))
      (node (ref "SJ9") (pin "2") (pinfunction "2_2") (pintype "passive"))
      (node (ref "U5") (pin "11") (pinfunction "VDDIO1_11") (pintype "power_in"))
      (node (ref "U5") (pin "39") (pinfunction "VDDBU_39") (pintype "power_in"))
      (node (ref "U5") (pin "43") (pinfunction "VDDIN_43") (pintype "power_in"))
      (node (ref "U5") (pin "72") (pinfunction "VDDIO2_72") (pintype "power_in"))
      (node (ref "U5") (pin "90") (pinfunction "VDDIO3_90") (pintype "power_in"))
    )
    (net (code "2") (name "+15V") (class "Default")
      (node (ref "C23") (pin "1") (pinfunction "1_1") (pintype "passive"))
      (node (ref "C31") (pin "1") (pinfunction "1_1") (pintype "passive"))
      (node (ref "C36") (pin "1") (pinfunction "1_1") (pintype "passive"))
      (node (ref "U1") (pin "2") (pinfunction "VDD_2") (pintype "power_in"))
      (node (ref "U3") (pin "2") (pinfunction "VDD_2") (pintype "power_in"))
      (node (ref "U4") (pin "1") (pinfunction "VOUT_1") (pintype "passive"))
    )
    (net (code "3") (name "/AD3") (class "Default")
      (node (ref "J6") (pin "13") (pinfunction "13_13") (pintype "passive"))
      (node (ref "U5") (pin "60") (pinfunction "PA6/TIOB2/NCS0/AD3_60") (pintype "bidirectional"))
    )
    (net (code "4") (name "/ADVREF") (class "Default")
      (node (ref "C25") (pin "1") (pinfunction "1_1") (pintype "passive"))
      (node (ref "L4") (pin "2") (pinfunction "2_2") (pintype "passive"))
      (node (ref "U5") (pin "53") (pinfunction "ADVREF_53") (pintype "power_in"))
    )
    (net (code "5") (name "/B-THERM") (class "Default")
      (node (ref "C40") (pin "2") (pinfunction "2_2") (pintype "passive"))
      (node (ref "J11") (pin "1") (pinfunction "1_1") (pintype "passive"))
      (node (ref "R18") (pin "1") (pinfunction "1_1") (pintype "passive"))
      (node (ref "U5") (pin "69") (pinfunction "PB20/TXD2/SPI0_NPCS1/AD13_69") (pintype "bidirectional"))
    )
    (net (code "6") (name "/E-STOP") (class "Default")
      (node (ref "JP10") (pin "1") (pinfunction "1_1") (pintype "passive"))
      (node (ref "U5") (pin "55") (pinfunction "PB16/TCLK5/PWML0/DAC1_55") (pintype "bidirectional"))
    )
    (net (code "7") (name "/E1-DIR") (class "Default")
      (node (ref "P4") (pin "DIR") (pinfunction "DIR_DIR") (pintype "bidirectional"))
      (node (ref "U5") (pin "96") (pinfunction "PB14/CANTX1/PWMH2_96") (pintype "bidirectional"))
    )
    (net (code "8") (name "/E1-STEP") (class "Default")
      (node (ref "P4") (pin "STEP") (pinfunction "STEP_STEP") (pintype "bidirectional"))
      (node (ref "U5") (pin "97") (pinfunction "PB22/RTS2/PCK0_97") (pintype "bidirectional"))
    )
    (net (code "9") (name "/E1-THERM") (class "Default")
      (node (ref "C39") (pin "2") (pinfunction "2_2") (pintype "passive"))
      (node (ref "J10") (pin "1") (pinfunction "1_1") (pintype "passive"))
      (node (ref "R17") (pin "1") (pinfunction "1_1") (pintype "passive"))
      (node (ref "U5") (pin "70") (pinfunction "PB21/RXD2.SPI0_NPCS2/AD14_70") (pintype "bidirectional"))
    )
    (net (code "10") (name "/ERASE") (class "Default")
      (node (ref "S2") (pin "1") (pinfunction "1_1") (pintype "passive"))
      (node (ref "U5") (pin "95") (pinfunction "PC0/ERASE_95") (pintype "bidirectional"))
    )
    (net (code "11") (name "/JTAG_TCK") (class "Default")
      (node (ref "JP4") (pin "4") (pinfunction "4_4") (pintype "passive"))
      (node (ref "U5") (pin "18") (pinfunction "PB28/TCK/SWCLK_18") (pintype "bidirectional"))
    )
    (net (code "12") (name "/JTAG_TDI") (class "Default")
      (node (ref "JP4") (pin "8") (pinfunction "8_8") (pintype "passive"))
      (node (ref "U5") (pin "19") (pinfunction "PB29/TDI_19") (pintype "bidirectional"))
    )
    (net (code "13") (name "/JTAG_TDO") (class "Default")
      (node (ref "JP4") (pin "6") (pinfunction "6_6") (pintype "passive"))
      (node (ref "U5") (pin "20") (pinfunction "PB30/TDO/TRACESWO_20") (pintype "bidirectional"))
    )
    (net (code "14") (name "/JTAG_TMS") (class "Default")
      (node (ref "JP4") (pin "2") (pinfunction "2_2") (pintype "passive"))
      (node (ref "U5") (pin "21") (pinfunction "PB31/TMS/SWDIO_21") (pintype "bidirectional"))
    )
    (net (code "15") (name "/MCCDA") (class "Default")
      (node (ref "J8") (pin "3") (pinfunction "CMD/DI_3") (pintype "input"))
      (node (ref "U5") (pin "50") (pinfunction "PA20/MCCDA/PWML2_50") (pintype "bidirectional"))
    )
    (net (code "16") (name "/MCCK") (class "Default")
      (node (ref "J8") (pin "5") (pinfunction "CLK_5") (pintype "input"))
      (node (ref "U5") (pin "49") (pinfunction "PA19/MCCK/PWMH1_49") (pintype "bidirectional"))
    )
    (net (code "17") (name "/MCDA0") (class "Default")
      (node (ref "J8") (pin "7") (pinfunction "DAT0/DO_7") (pintype "bidirectional"))
      (node (ref "U5") (pin "74") (pinfunction "PA21/MCDA0/PWML0_74") (pintype "bidirectional"))
    )
    (net (code "18") (name "/MCDA1") (class "Default")
      (node (ref "J8") (pin "8") (pinfunction "DAT1_8") (pintype "bidirectional"))
      (node (ref "U5") (pin "59") (pinfunction "PA22/MCDA1/TCLK3/AD4_59") (pintype "bidirectional"))
    )
    (net (code "19") (name "/MCDA2") (class "Default")
      (node (ref "J8") (pin "1") (pinfunction "DAT2_1") (pintype "bidirectional"))
      (node (ref "U5") (pin "58") (pinfunction "PA23/MCDA2/TCLK4/AD5_58") (pintype "bidirectional"))
    )
    (net (code "20") (name "/MCDA3") (class "Default")
      (node (ref "J8") (pin "2") (pinfunction "DAT3/CS_2") (pintype "bidirectional"))
      (node (ref "U5") (pin "57") (pinfunction "PA24/MCDA3/PCK1/AD6_57") (pintype "bidirectional"))
    )
    (net (code "21") (name "/MISO") (class "Default")
      (node (ref "JP5") (pin "6") (pinfunction "6_6") (pintype "passive"))
      (node (ref "U5") (pin "75") (pinfunction "PA25/SPI0_MISO/A18_75") (pintype "bidirectional"))
    )
    (net (code "22") (name "/MOSI") (class "Default")
      (node (ref "JP5") (pin "3") (pinfunction "3_3") (pintype "passive"))
      (node (ref "U5") (pin "76") (pinfunction "PA26/SPI0_MOSI/A19_76") (pintype "bidirectional"))
    )
    (net (code "23") (name "/PA2") (class "Default")
      (node (ref "J6") (pin "12") (pinfunction "12_12") (pintype "passive"))
      (node (ref "U5") (pin "63") (pinfunction "PA2/TIOA1/NANDRDY/AD0_63") (pintype "bidirectional"))
    )
    (net (code "24") (name "/PA3") (class "Default")
      (node (ref "J6") (pin "11") (pinfunction "11_11") (pintype "passive"))
      (node (ref "U5") (pin "62") (pinfunction "PA3/TIOB1/PWMFI0/WKUP1_62") (pintype "bidirectional"))
    )
    (net (code "25") (name "/PA4") (class "Default")
      (node (ref "J6") (pin "14") (pinfunction "14_14") (pintype "passive"))
      (node (ref "U5") (pin "61") (pinfunction "PA4/TCLK1/NWAIT/AD2_61") (pintype "bidirectional"))
    )
    (net (code "26") (name "/PA15") (class "Default")
      (node (ref "U5") (pin "8") (pinfunction "PA15/CTS1/TF/WKUP8_8") (pintype "bidirectional"))
    )
    (net (code "27") (name "/PA17") (class "Default")
      (node (ref "U5") (pin "9") (pinfunction "PA17/TWD0/SPCK0_9") (pintype "bidirectional"))
    )
    (net (code "28") (name "/PA28") (class "Default")
      (node (ref "J6") (pin "5") (pinfunction "5_5") (pintype "passive"))
      (node (ref "U5") (pin "78") (pinfunction "PA28/SPI0_NPCS0/PCK2/WKUP11_78") (pintype "bidirectional"))
    )
    (net (code "29") (name "/PA29") (class "Default")
      (node (ref "J6") (pin "4") (pinfunction "4_4") (pintype "passive"))
      (node (ref "U5") (pin "79") (pinfunction "PA29/SPI0_NPCS1/NRD_79") (pintype "bidirectional"))
    )
    (net (code "30") (name "/PB12") (class "Default")
      (node (ref "J6") (pin "9") (pinfunction "9_9") (pintype "passive"))
      (node (ref "U5") (pin "64") (pinfunction "PB12/TWD1/PWMH0/AD8_64") (pintype "bidirectional"))
    )
    (net (code "31") (name "/PB13") (class "Default")
      (node (ref "J6") (pin "10") (pinfunction "10_10") (pintype "passive"))
      (node (ref "U5") (pin "65") (pinfunction "PB13/TWCK1/PWMH1/AD9_65") (pintype "bidirectional"))
    )
    (net (code "32") (name "/PB17") (class "Default")
      (node (ref "J6") (pin "8") (pinfunction "8_8") (pintype "passive"))
      (node (ref "U5") (pin "66") (pinfunction "PB17/RF/PWML1/AD10_66") (pintype "bidirectional"))
    )
    (net (code "33") (name "/PB18") (class "Default")
      (node (ref "J6") (pin "6") (pinfunction "6_6") (pintype "passive"))
      (node (ref "U5") (pin "67") (pinfunction "PB18/RD/PWML2/AD11_67") (pintype "bidirectional"))
    )
    (net (code "34") (name "/PB19") (class "Default")
      (node (ref "J6") (pin "7") (pinfunction "7_7") (pintype "passive"))
      (node (ref "U5") (pin "68") (pinfunction "PB19/RK/PWML3/AD12_68") (pintype "bidirectional"))
    )
    (net (code "35") (name "/SCLK") (class "Default")
      (node (ref "JP5") (pin "4") (pinfunction "4_4") (pintype "passive"))
      (node (ref "U5") (pin "77") (pinfunction "PA27/SPI0_SPCK/A20/WKUP10_77") (pintype "bidirectional"))
    )
    (net (code "36") (name "/SDCD") (class "Default")
      (node (ref "J8") (pin "CD2") (pinfunction "CD2_CD2") (pintype "bidirectional"))
      (node (ref "U5") (pin "48") (pinfunction "PA18/TWCK0/A20/WKUP9_48") (pintype "bidirectional"))
    )
    (net (code "37") (name "/USB_DN") (class "Default")
      (node (ref "J9") (pin "D-") (pinfunction "D-_D-") (pintype "bidirectional"))
      (node (ref "R10") (pin "1") (pinfunction "1_1") (pintype "passive"))
      (node (ref "U5") (pin "27") (pinfunction "DHSDM_27") (pintype "bidirectional"))
      (node (ref "U6") (pin "3") (pinfunction "IO2_3") (pintype "bidirectional"))
    )
    (net (code "38") (name "/USB_DP") (class "Default")
      (node (ref "J9") (pin "D+") (pinfunction "D+_D+") (pintype "bidirectional"))
      (node (ref "R11") (pin "1") (pinfunction "1_1") (pintype "passive"))
      (node (ref "U5") (pin "26") (pinfunction "DHSDP_26") (pintype "bidirectional"))
      (node (ref "U6") (pin "2") (pinfunction "IO1_2") (pintype "bidirectional"))
    )
    (net (code "39") (name "/VBUS") (class "Default")
      (node (ref "C41") (pin "2") (pinfunction "2_2") (pintype "passive"))
      (node (ref "J9") (pin "VBUS") (pinfunction "VBUS_VBUS") (pintype "bidirectional"))
      (node (ref "U5") (pin "28") (pinfunction "VBUS_28") (pintype "power_in"))
      (node (ref "U6") (pin "4") (pinfunction "VCC_4") (pintype "power_in"))
    )
    (net (code "40") (name "/VDDANA") (class "Default")
      (node (ref "C10") (pin "1") (pinfunction "1_1") (pintype "passive"))
      (node (ref "C6") (pin "1") (pinfunction "1_1") (pintype "passive"))
      (node (ref "L1") (pin "2") (pinfunction "2_2") (pintype "passive"))
      (node (ref "U5") (pin "51") (pinfunction "VDDANA_51") (pintype "power_in"))
    )
    (net (code "41") (name "/VDDPLL") (class "Default")
      (node (ref "C11") (pin "1") (pinfunction "1_1") (pintype "passive"))
      (node (ref "C7") (pin "1") (pinfunction "1_1") (pintype "passive"))
      (node (ref "L2") (pin "2") (pinfunction "2_2") (pintype "passive"))
      (node (ref "U5") (pin "23") (pinfunction "VDDPLL_23") (pintype "input"))
    )
    (net (code "42") (name "/VDDUTMI") (class "Default")
      (node (ref "C21") (pin "1") (pinfunction "1_1") (pintype "passive"))
      (node (ref "C24") (pin "1") (pinfunction "1_1") (pintype "passive"))
      (node (ref "L3") (pin "2") (pinfunction "2_2") (pintype "passive"))
      (node (ref "U5") (pin "30") (pinfunction "VDDUTMI_30") (pintype "input"))
    )
    (net (code "43") (name "/X-DIR") (class "Default")
      (node (ref "P1") (pin "DIR") (pinfunction "DIR_DIR") (pintype "bidirectional"))
      (node (ref "U5") (pin "5") (pinfunction "PA12/RXD1/PWML1/WKUP7_5") (pintype "bidirectional"))
    )
    (net (code "44") (name "/X-STEP") (class "Default")
      (node (ref "P1") (pin "STEP") (pinfunction "STEP_STEP") (pintype "bidirectional"))
      (node (ref "U5") (pin "6") (pinfunction "PA13/TXD1/PWMH2_6") (pintype "bidirectional"))
    )
    (net (code "45") (name "/X-STOP") (class "Default")
      (node (ref "JP8") (pin "1") (pinfunction "1_1") (pintype "passive"))
      (node (ref "U5") (pin "54") (pinfunction "PB15/CANRX1/PWMH3/DAC0_54") (pintype "bidirectional"))
    )
    (net (code "46") (name "/XTAL1") (class "Default")
      (node (ref "C35") (pin "2") (pinfunction "2_2") (pintype "passive"))
      (node (ref "U5") (pin "25") (pinfunction "XIN_25") (pintype "input"))
      (node (ref "X1") (pin "P$2") (pinfunction "2_P$2") (pintype "passive"))
    )
    (net (code "47") (name "/XTAL2") (class "Default")
      (node (ref "C34") (pin "2") (pinfunction "2_2") (pintype "passive"))
      (node (ref "U5") (pin "24") (pinfunction "XOUT_24") (pintype "output"))
      (node (ref "X1") (pin "P$1") (pinfunction "1_P$1") (pintype "passive"))
    )
    (net (code "48") (name "/Y-DIR") (class "Default")
      (node (ref "P2") (pin "DIR") (pinfunction "DIR_DIR") (pintype "bidirectional"))
      (node (ref "U5") (pin "2") (pinfunction "PA9/UTXD/PWMH3_2") (pintype "bidirectional"))
    )
    (net (code "49") (name "/Y-STEP") (class "Default")
      (node (ref "P2") (pin "STEP") (pinfunction "STEP_STEP") (pintype "bidirectional"))
      (node (ref "U5") (pin "3") (pinfunction "PA10/RXD0/DATRG/WKUP5_3") (pintype "bidirectional"))
    )
    (net (code "50") (name "/Y-STOP") (class "Default")
      (node (ref "JP9") (pin "1") (pinfunction "1_1") (pintype "passive"))
      (node (ref "U5") (pin "16") (pinfunction "PA7/TCLK2/NCS1/WKUP3_16") (pintype "bidirectional"))
    )
    (net (code "51") (name "/Z-DIR") (class "Default")
      (node (ref "P3") (pin "DIR") (pinfunction "DIR_DIR") (pintype "bidirectional"))
      (node (ref "U5") (pin "99") (pinfunction "PB24/SCK2/NCS2_99") (pintype "bidirectional"))
    )
    (net (code "52") (name "/Z-STEP") (class "Default")
      (node (ref "P3") (pin "STEP") (pinfunction "STEP_STEP") (pintype "bidirectional"))
      (node (ref "U5") (pin "100") (pinfunction "PB25/RTS0/TIOA0_100") (pintype "bidirectional"))
    )
    (net (code "53") (name "/Z-STOP") (class "Default")
      (node (ref "Q4") (pin "3") (pinfunction "C_3") (pintype "passive"))
      (node (ref "U5") (pin "17") (pinfunction "PA8/URXD/PWMH0/WKUP4_17") (pintype "bidirectional"))
    )
    (net (code "54") (name "/~{E1-ENABLE}") (class "Default")
      (node (ref "P4") (pin "!EN") (pinfunction "~{ENABLE}_!EN") (pintype "input"))
      (node (ref "R22") (pin "2") (pinfunction "2_2") (pintype "passive"))
      (node (ref "U5") (pin "98") (pinfunction "PB23/CTS2.SPI0_NPCS3/WKUP14_98") (pintype "bidirectional"))
    )
    (net (code "55") (name "/~{HOTBED}") (class "Default")
      (node (ref "R15") (pin "1") (pinfunction "1_1") (pintype "passive"))
      (node (ref "U3") (pin "3") (pinfunction "IN_3") (pintype "input"))
      (node (ref "U5") (pin "15") (pinfunction "PA5/TIOA2/PWMFI0/WKUP2_15") (pintype "bidirectional"))
    )
    (net (code "56") (name "/~{HOTEND-1}") (class "Default")
      (node (ref "R4") (pin "1") (pinfunction "1_1") (pintype "passive"))
      (node (ref "U1") (pin "3") (pinfunction "IN_3") (pintype "input"))
      (node (ref "U5") (pin "14") (pinfunction "PA1/CANRX0/PCK0/WKUP0_14") (pintype "bidirectional"))
    )
    (net (code "57") (name "/~{PWM-FAN}") (class "Default")
      (node (ref "R2") (pin "1") (pinfunction "1_1") (pintype "passive"))
      (node (ref "R3") (pin "1") (pinfunction "1_1") (pintype "passive"))
      (node (ref "U5") (pin "85") (pinfunction "PB5/TIOB5_85") (pintype "bidirectional"))
    )
    (net (code "58") (name "/~{RESET}") (class "Default")
      (node (ref "JP4") (pin "10") (pinfunction "10_10") (pintype "passive"))
      (node (ref "JP5") (pin "2") (pinfunction "2_2") (pintype "passive"))
      (node (ref "S1") (pin "1") (pinfunction "1_1") (pintype "passive"))
      (node (ref "U5") (pin "47") (pinfunction "~{NRST}_47") (pintype "bidirectional"))
    )
    (net (code "59") (name "/~{X-ENABLE}") (class "Default")
      (node (ref "P1") (pin "!EN") (pinfunction "~{ENABLE}_!EN") (pintype "input"))
      (node (ref "R20") (pin "2") (pinfunction "2_2") (pintype "passive"))
      (node (ref "U5") (pin "7") (pinfunction "PA14/RTS1/TK_7") (pintype "bidirectional"))
    )
    (net (code "60") (name "/~{Y-ENABLE}") (class "Default")
      (node (ref "P2") (pin "!EN") (pinfunction "~{ENABLE}_!EN") (pintype "input"))
      (node (ref "R19") (pin "2") (pinfunction "2_2") (pintype "passive"))
      (node (ref "U5") (pin "4") (pinfunction "PA11/TXD0/ADTRG/WKUP6_4") (pintype "bidirectional"))
    )
    (net (code "61") (name "/~{Z-ENABLE}") (class "Default")
      (node (ref "P3") (pin "!EN") (pinfunction "~{ENABLE}_!EN") (pintype "input"))
      (node (ref "R21") (pin "2") (pinfunction "2_2") (pintype "passive"))
      (node (ref "U5") (pin "1") (pinfunction "PB26/CTS0/TCLK0/WKUP15_1") (pintype "bidirectional"))
    )
    (net (code "62") (name "24V") (class "Default")
      (node (ref "C20") (pin "1") (pinfunction "1_1") (pintype "passive"))
      (node (ref "C29") (pin "+") (pinfunction "+_+") (pintype "passive"))
      (node (ref "C33") (pin "1") (pinfunction "1_1") (pintype "passive"))
      (node (ref "C37") (pin "+") (pinfunction "+_+") (pintype "passive"))
      (node (ref "C42") (pin "+") (pinfunction "+_+") (pintype "passive"))
      (node (ref "C43") (pin "+") (pinfunction "+_+") (pintype "passive"))
      (node (ref "C44") (pin "+") (pinfunction "+_+") (pintype "passive"))
      (node (ref "C45") (pin "+") (pinfunction "+_+") (pintype "passive"))
      (node (ref "F1") (pin "P$3") (pinfunction "P$3_P$3") (pintype "passive"))
      (node (ref "F1") (pin "P$4") (pinfunction "P$4_P$4") (pintype "passive"))
      (node (ref "J2") (pin "1") (pinfunction "1_1") (pintype "passive"))
      (node (ref "J3") (pin "1") (pinfunction "1_1") (pintype "passive"))
      (node (ref "J4") (pin "1") (pinfunction "1_1") (pintype "passive"))
      (node (ref "J5") (pin "3") (pinfunction "3_3") (pintype "power_in"))
      (node (ref "J5") (pin "4") (pinfunction "4_4") (pintype "power_in"))
      (node (ref "J6") (pin "3") (pinfunction "3_3") (pintype "passive"))
      (node (ref "J7") (pin "3") (pinfunction "3_3") (pintype "power_in"))
      (node (ref "J7") (pin "4") (pinfunction "4_4") (pintype "power_in"))
      (node (ref "JP6") (pin "1") (pinfunction "1_1") (pintype "passive"))
      (node (ref "JP7") (pin "4") (pinfunction "4_4") (pintype "passive"))
      (node (ref "P1") (pin "VMOT") (pinfunction "VMOT_VMOT") (pintype "power_in"))
      (node (ref "P2") (pin "VMOT") (pinfunction "VMOT_VMOT") (pintype "power_in"))
      (node (ref "P3") (pin "VMOT") (pinfunction "VMOT_VMOT") (pintype "power_in"))
      (node (ref "P4") (pin "VMOT") (pinfunction "VMOT_VMOT") (pintype "power_in"))
      (node (ref "R5") (pin "1") (pinfunction "1_1") (pintype "passive"))
      (node (ref "U2") (pin "5") (pinfunction "VIN_5") (pintype "power_in"))
      (node (ref "U4") (pin "3") (pinfunction "VIN_3") (pintype "power_in"))
    )
    (net (code "63") (name "GND") (class "Default")
      (node (ref "C1") (pin "2") (pinfunction "2_2") (pintype "passive"))
      (node (ref "C10") (pin "2") (pinfunction "2_2") (pintype "passive"))
      (node (ref "C11") (pin "2") (pinfunction "2_2") (pintype "passive"))
      (node (ref "C12") (pin "2") (pinfunction "2_2") (pintype "passive"))
      (node (ref "C13") (pin "2") (pinfunction "2_2") (pintype "passive"))
      (node (ref "C14") (pin "2") (pinfunction "2_2") (pintype "passive"))
      (node (ref "C15") (pin "2") (pinfunction "2_2") (pintype "passive"))
      (node (ref "C16") (pin "2") (pinfunction "2_2") (pintype "passive"))
      (node (ref "C17") (pin "2") (pinfunction "2_2") (pintype "passive"))
      (node (ref "C18") (pin "2") (pinfunction "2_2") (pintype "passive"))
      (node (ref "C19") (pin "2") (pinfunction "2_2") (pintype "passive"))
      (node (ref "C2") (pin "2") (pinfunction "2_2") (pintype "passive"))
      (node (ref "C20") (pin "2") (pinfunction "2_2") (pintype "passive"))
      (node (ref "C21") (pin "2") (pinfunction "2_2") (pintype "passive"))
      (node (ref "C22") (pin "2") (pinfunction "2_2") (pintype "passive"))
      (node (ref "C23") (pin "2") (pinfunction "2_2") (pintype "passive"))
      (node (ref "C24") (pin "2") (pinfunction "2_2") (pintype "passive"))
      (node (ref "C25") (pin "2") (pinfunction "2_2") (pintype "passive"))
      (node (ref "C26") (pin "2") (pinfunction "2_2") (pintype "passive"))
      (node (ref "C27") (pin "2") (pinfunction "2_2") (pintype "passive"))
      (node (ref "C29") (pin "-") (pinfunction "-_-") (pintype "passive"))
      (node (ref "C3") (pin "2") (pinfunction "2_2") (pintype "passive"))
      (node (ref "C30") (pin "2") (pinfunction "2_2") (pintype "passive"))
      (node (ref "C31") (pin "2") (pinfunction "2_2") (pintype "passive"))
      (node (ref "C32") (pin "2") (pinfunction "2_2") (pintype "passive"))
      (node (ref "C33") (pin "2") (pinfunction "2_2") (pintype "passive"))
      (node (ref "C34") (pin "1") (pinfunction "1_1") (pintype "passive"))
      (node (ref "C35") (pin "1") (pinfunction "1_1") (pintype "passive"))
      (node (ref "C36") (pin "2") (pinfunction "2_2") (pintype "passive"))
      (node (ref "C37") (pin "-") (pinfunction "-_-") (pintype "passive"))
      (node (ref "C38") (pin "2") (pinfunction "2_2") (pintype "passive"))
      (node (ref "C39") (pin "1") (pinfunction "1_1") (pintype "passive"))
      (node (ref "C4") (pin "2") (pinfunction "2_2") (pintype "passive"))
      (node (ref "C40") (pin "1") (pinfunction "1_1") (pintype "passive"))
      (node (ref "C41") (pin "1") (pinfunction "1_1") (pintype "passive"))
      (node (ref "C42") (pin "-") (pinfunction "-_-") (pintype "passive"))
      (node (ref "C43") (pin "-") (pinfunction "-_-") (pintype "passive"))
      (node (ref "C44") (pin "-") (pinfunction "-_-") (pintype "passive"))
      (node (ref "C45") (pin "-") (pinfunction "-_-") (pintype "passive"))
      (node (ref "C5") (pin "2") (pinfunction "2_2") (pintype "passive"))
      (node (ref "C6") (pin "2") (pinfunction "2_2") (pintype "passive"))
      (node (ref "C7") (pin "2") (pinfunction "2_2") (pintype "passive"))
      (node (ref "C8") (pin "2") (pinfunction "2_2") (pintype "passive"))
      (node (ref "C9") (pin "2") (pinfunction "2_2") (pintype "passive"))
      (node (ref "D1") (pin "A") (pinfunction "A_A") (pintype "passive"))
      (node (ref "D2") (pin "A") (pinfunction "A_A") (pintype "passive"))
      (node (ref "J1") (pin "3") (pinfunction "3_3") (pintype "power_in"))
      (node (ref "J1") (pin "4") (pinfunction "4_4") (pintype "power_in"))
      (node (ref "J10") (pin "2") (pinfunction "2_2") (pintype "passive"))
      (node (ref "J11") (pin "2") (pinfunction "2_2") (pintype "passive"))
      (node (ref "J2") (pin "2") (pinfunction "2_2") (pintype "passive"))
      (node (ref "J3") (pin "2") (pinfunction "2_2") (pintype "passive"))
      (node (ref "J6") (pin "1") (pinfunction "1_1") (pintype "passive"))
      (node (ref "J8") (pin "6") (pinfunction "GND_6") (pintype "power_in"))
      (node (ref "J8") (pin "C1") (pinfunction "SHEILD_C1") (pintype "bidirectional"))
      (node (ref "J8") (pin "C2") (pinfunction "SHIELD_C2") (pintype "bidirectional"))
      (node (ref "J8") (pin "C3") (pinfunction "SHIELD_C3") (pintype "bidirectional"))
      (node (ref "J8") (pin "C4") (pinfunction "SHIELD_C4") (pintype "bidirectional"))
      (node (ref "J8") (pin "CD1") (pinfunction "CD1_CD1") (pintype "bidirectional"))
      (node (ref "J9") (pin "GND") (pinfunction "GND_GND") (pintype "bidirectional"))
      (node (ref "J9") (pin "GND1") (pinfunction "GND_GND1") (pintype "bidirectional"))
      (node (ref "J9") (pin "GND2") (pinfunction "GND_GND2") (pintype "bidirectional"))
      (node (ref "J9") (pin "GND3") (pinfunction "GND_GND3") (pintype "bidirectional"))
      (node (ref "J9") (pin "GND4") (pinfunction "GND_GND4") (pintype "bidirectional"))
      (node (ref "J9") (pin "GND5") (pinfunction "GND_GND5") (pintype "bidirectional"))
      (node (ref "J9") (pin "GND6") (pinfunction "GND_GND6") (pintype "bidirectional"))
      (node (ref "J9") (pin "GND7") (pinfunction "GND_GND7") (pintype "bidirectional"))
      (node (ref "J9") (pin "GND8") (pinfunction "GND_GND8") (pintype "bidirectional"))
      (node (ref "JP10") (pin "3") (pinfunction "3_3") (pintype "passive"))
      (node (ref "JP4") (pin "3") (pinfunction "3_3") (pintype "passive"))
      (node (ref "JP4") (pin "5") (pinfunction "5_5") (pintype "passive"))
      (node (ref "JP4") (pin "9") (pinfunction "9_9") (pintype "passive"))
      (node (ref "JP5") (pin "1") (pinfunction "1_1") (pintype "passive"))
      (node (ref "JP7") (pin "3") (pinfunction "3_3") (pintype "passive"))
      (node (ref "JP8") (pin "3") (pinfunction "3_3") (pintype "passive"))
      (node (ref "JP9") (pin "3") (pinfunction "3_3") (pintype "passive"))
      (node (ref "LED1") (pin "C") (pinfunction "C_C") (pintype "passive"))
      (node (ref "P1") (pin "GNDMOT") (pinfunction "GNDMOT_GNDMOT") (pintype "power_in"))
      (node (ref "P1") (pin "GNDVDD") (pinfunction "GNDVDD_GNDVDD") (pintype "power_in"))
      (node (ref "P2") (pin "GNDMOT") (pinfunction "GNDMOT_GNDMOT") (pintype "power_in"))
      (node (ref "P2") (pin "GNDVDD") (pinfunction "GNDVDD_GNDVDD") (pintype "power_in"))
      (node (ref "P3") (pin "GNDMOT") (pinfunction "GNDMOT_GNDMOT") (pintype "power_in"))
      (node (ref "P3") (pin "GNDVDD") (pinfunction "GNDVDD_GNDVDD") (pintype "power_in"))
      (node (ref "P4") (pin "GNDMOT") (pinfunction "GNDMOT_GNDMOT") (pintype "power_in"))
      (node (ref "P4") (pin "GNDVDD") (pinfunction "GNDVDD_GNDVDD") (pintype "power_in"))
      (node (ref "Q1") (pin "2") (pinfunction "S_2") (pintype "passive"))
      (node (ref "Q2") (pin "1") (pinfunction "S1_1") (pintype "passive"))
      (node (ref "Q2") (pin "2") (pinfunction "S2_2") (pintype "passive"))
      (node (ref "Q2") (pin "3") (pinfunction "S3_3") (pintype "passive"))
      (node (ref "Q3") (pin "1") (pinfunction "S1_1") (pintype "passive"))
      (node (ref "Q3") (pin "2") (pinfunction "S2_2") (pintype "passive"))
      (node (ref "Q3") (pin "3") (pinfunction "S3_3") (pintype "passive"))
      (node (ref "Q4") (pin "2") (pinfunction "E_2") (pintype "passive"))
      (node (ref "R12") (pin "2") (pinfunction "2_2") (pintype "passive"))
      (node (ref "R14") (pin "2") (pinfunction "2_2") (pintype "passive"))
      (node (ref "R15") (pin "2") (pinfunction "2_2") (pintype "passive"))
      (node (ref "R2") (pin "2") (pinfunction "2_2") (pintype "passive"))
      (node (ref "R4") (pin "2") (pinfunction "2_2") (pintype "passive"))
      (node (ref "R6") (pin "2") (pinfunction "2_2") (pintype "passive"))
      (node (ref "R8") (pin "1") (pinfunction "1_1") (pintype "passive"))
      (node (ref "S1") (pin "2") (pinfunction "2_2") (pintype "passive"))
      (node (ref "SCREW1") (pin "GND") (pinfunction "P$1_GND") (pintype "bidirectional"))
      (node (ref "SCREW2") (pin "GND") (pinfunction "P$1_GND") (pintype "bidirectional"))
      (node (ref "SCREW3") (pin "GND") (pinfunction "P$1_GND") (pintype "bidirectional"))
      (node (ref "SCREW4") (pin "GND") (pinfunction "P$1_GND") (pintype "bidirectional"))
      (node (ref "U1") (pin "1") (pinfunction "GND1_1") (pintype "passive"))
      (node (ref "U1") (pin "4") (pinfunction "GND2_4") (pintype "passive"))
      (node (ref "U2") (pin "2") (pinfunction "GND_2") (pintype "power_in"))
      (node (ref "U3") (pin "1") (pinfunction "GND1_1") (pintype "passive"))
      (node (ref "U3") (pin "4") (pinfunction "GND2_4") (pintype "passive"))
      (node (ref "U4") (pin "2") (pinfunction "GND_2") (pintype "passive"))
      (node (ref "U5") (pin "12") (pinfunction "GND1_12") (pintype "power_in"))
      (node (ref "U5") (pin "22") (pinfunction "GNDPLL_22") (pintype "power_in"))
      (node (ref "U5") (pin "33") (pinfunction "GNDUTMI_33") (pintype "power_in"))
      (node (ref "U5") (pin "35") (pinfunction "JTAGSEL_35") (pintype "input"))
      (node (ref "U5") (pin "41") (pinfunction "GND2_41") (pintype "power_in"))
      (node (ref "U5") (pin "44") (pinfunction "GND3_44") (pintype "power_in"))
      (node (ref "U5") (pin "52") (pinfunction "GNDANA_52") (pintype "power_in"))
      (node (ref "U5") (pin "73") (pinfunction "GND4_73") (pintype "power_in"))
      (node (ref "U5") (pin "91") (pinfunction "GND5_91") (pintype "power_in"))
      (node (ref "U6") (pin "1") (pinfunction "GND_1") (pintype "power_in"))
    )
    (net (code "64") (name "Net-(F1-PadP$1)") (class "Default")
      (node (ref "F1") (pin "P$1") (pinfunction "P$1_P$1") (pintype "passive"))
      (node (ref "F1") (pin "P$2") (pinfunction "P$2_P$2") (pintype "passive"))
      (node (ref "J1") (pin "1") (pinfunction "1_1") (pintype "power_in"))
      (node (ref "J1") (pin "2") (pinfunction "2_2") (pintype "power_in"))
    )
    (net (code "65") (name "Net-(F2-PadP$2)") (class "Default")
      (node (ref "F2") (pin "P$2") (pinfunction "P$2_P$2") (pintype "passive"))
      (node (ref "J4") (pin "2") (pinfunction "2_2") (pintype "passive"))
    )
    (net (code "66") (name "Net-(JP10-Pad2)") (class "Default")
      (node (ref "JP10") (pin "2") (pinfunction "2_2") (pintype "passive"))
      (node (ref "JP6") (pin "2") (pinfunction "2_2") (pintype "passive"))
      (node (ref "JP8") (pin "2") (pinfunction "2_2") (pintype "passive"))
      (node (ref "JP9") (pin "2") (pinfunction "2_2") (pintype "passive"))
    )
    (net (code "67") (name "Net-(LED1-PadA)") (class "Default")
      (node (ref "LED1") (pin "A") (pinfunction "A_A") (pintype "passive"))
      (node (ref "R1") (pin "1") (pinfunction "1_1") (pintype "passive"))
    )
    (net (code "68") (name "Net-(P1-MOT-1A)") (class "Default")
      (node (ref "JP11") (pin "3") (pinfunction "3_3") (pintype "passive"))
      (node (ref "P1") (pin "1A") (pinfunction "MOT-1A_1A") (pintype "power_in"))
    )
    (net (code "69") (name "Net-(P1-MOT-1B)") (class "Default")
      (node (ref "JP11") (pin "4") (pinfunction "4_4") (pintype "passive"))
      (node (ref "P1") (pin "1B") (pinfunction "MOT-1B_1B") (pintype "power_in"))
    )
    (net (code "70") (name "Net-(P1-MOT-2A)") (class "Default")
      (node (ref "JP11") (pin "2") (pinfunction "2_2") (pintype "passive"))
      (node (ref "P1") (pin "2A") (pinfunction "MOT-2A_2A") (pintype "power_in"))
    )
    (net (code "71") (name "Net-(P1-MOT-2B)") (class "Default")
      (node (ref "JP11") (pin "1") (pinfunction "1_1") (pintype "passive"))
      (node (ref "P1") (pin "2B") (pinfunction "MOT-2B_2B") (pintype "power_in"))
    )
    (net (code "72") (name "Net-(P1-PadMS1)") (class "Default")
      (node (ref "P1") (pin "MS1") (pinfunction "MS1_MS1") (pintype "input"))
      (node (ref "SJ9") (pin "1") (pinfunction "1_1") (pintype "passive"))
    )
    (net (code "73") (name "Net-(P1-PadMS2)") (class "Default")
      (node (ref "P1") (pin "MS2") (pinfunction "MS2_MS2") (pintype "input"))
      (node (ref "SJ5") (pin "1") (pinfunction "1_1") (pintype "passive"))
    )
    (net (code "74") (name "Net-(P1-PadMS3)") (class "Default")
      (node (ref "P1") (pin "MS3") (pinfunction "MS3_MS3") (pintype "input"))
      (node (ref "SJ1") (pin "1") (pinfunction "1_1") (pintype "passive"))
    )
    (net (code "75") (name "Net-(P1-~{RESET})") (class "Default")
      (node (ref "P1") (pin "!RST") (pinfunction "~{RESET}_!RST") (pintype "input"))
      (node (ref "P1") (pin "!SLP") (pinfunction "~{SLEEP}_!SLP") (pintype "input"))
    )
    (net (code "76") (name "Net-(P2-MOT-1A)") (class "Default")
      (node (ref "JP12") (pin "3") (pinfunction "3_3") (pintype "passive"))
      (node (ref "P2") (pin "1A") (pinfunction "MOT-1A_1A") (pintype "power_in"))
    )
    (net (code "77") (name "Net-(P2-MOT-1B)") (class "Default")
      (node (ref "JP12") (pin "4") (pinfunction "4_4") (pintype "passive"))
      (node (ref "P2") (pin "1B") (pinfunction "MOT-1B_1B") (pintype "power_in"))
    )
    (net (code "78") (name "Net-(P2-MOT-2A)") (class "Default")
      (node (ref "JP12") (pin "2") (pinfunction "2_2") (pintype "passive"))
      (node (ref "P2") (pin "2A") (pinfunction "MOT-2A_2A") (pintype "power_in"))
    )
    (net (code "79") (name "Net-(P2-MOT-2B)") (class "Default")
      (node (ref "JP12") (pin "1") (pinfunction "1_1") (pintype "passive"))
      (node (ref "P2") (pin "2B") (pinfunction "MOT-2B_2B") (pintype "power_in"))
    )
    (net (code "80") (name "Net-(P2-PadMS1)") (class "Default")
      (node (ref "P2") (pin "MS1") (pinfunction "MS1_MS1") (pintype "input"))
      (node (ref "SJ10") (pin "1") (pinfunction "1_1") (pintype "passive"))
    )
    (net (code "81") (name "Net-(P2-PadMS2)") (class "Default")
      (node (ref "P2") (pin "MS2") (pinfunction "MS2_MS2") (pintype "input"))
      (node (ref "SJ6") (pin "1") (pinfunction "1_1") (pintype "passive"))
    )
    (net (code "82") (name "Net-(P2-PadMS3)") (class "Default")
      (node (ref "P2") (pin "MS3") (pinfunction "MS3_MS3") (pintype "input"))
      (node (ref "SJ2") (pin "1") (pinfunction "1_1") (pintype "passive"))
    )
    (net (code "83") (name "Net-(P2-~{RESET})") (class "Default")
      (node (ref "P2") (pin "!RST") (pinfunction "~{RESET}_!RST") (pintype "input"))
      (node (ref "P2") (pin "!SLP") (pinfunction "~{SLEEP}_!SLP") (pintype "input"))
    )
    (net (code "84") (name "Net-(P3-MOT-1A)") (class "Default")
      (node (ref "JP14") (pin "3") (pinfunction "3_3") (pintype "passive"))
      (node (ref "P3") (pin "1A") (pinfunction "MOT-1A_1A") (pintype "power_in"))
    )
    (net (code "85") (name "Net-(P3-MOT-1B)") (class "Default")
      (node (ref "JP14") (pin "4") (pinfunction "4_4") (pintype "passive"))
      (node (ref "P3") (pin "1B") (pinfunction "MOT-1B_1B") (pintype "power_in"))
    )
    (net (code "86") (name "Net-(P3-MOT-2A)") (class "Default")
      (node (ref "JP14") (pin "2") (pinfunction "2_2") (pintype "passive"))
      (node (ref "P3") (pin "2A") (pinfunction "MOT-2A_2A") (pintype "power_in"))
    )
    (net (code "87") (name "Net-(P3-MOT-2B)") (class "Default")
      (node (ref "JP14") (pin "1") (pinfunction "1_1") (pintype "passive"))
      (node (ref "P3") (pin "2B") (pinfunction "MOT-2B_2B") (pintype "power_in"))
    )
    (net (code "88") (name "Net-(P3-PadMS1)") (class "Default")
      (node (ref "P3") (pin "MS1") (pinfunction "MS1_MS1") (pintype "input"))
      (node (ref "SJ11") (pin "1") (pinfunction "1_1") (pintype "passive"))
    )
    (net (code "89") (name "Net-(P3-PadMS2)") (class "Default")
      (node (ref "P3") (pin "MS2") (pinfunction "MS2_MS2") (pintype "input"))
      (node (ref "SJ7") (pin "1") (pinfunction "1_1") (pintype "passive"))
    )
    (net (code "90") (name "Net-(P3-PadMS3)") (class "Default")
      (node (ref "P3") (pin "MS3") (pinfunction "MS3_MS3") (pintype "input"))
      (node (ref "SJ3") (pin "1") (pinfunction "1_1") (pintype "passive"))
    )
    (net (code "91") (name "Net-(P3-~{RESET})") (class "Default")
      (node (ref "P3") (pin "!RST") (pinfunction "~{RESET}_!RST") (pintype "input"))
      (node (ref "P3") (pin "!SLP") (pinfunction "~{SLEEP}_!SLP") (pintype "input"))
    )
    (net (code "92") (name "Net-(P4-MOT-1A)") (class "Default")
      (node (ref "JP13") (pin "3") (pinfunction "3_3") (pintype "passive"))
      (node (ref "P4") (pin "1A") (pinfunction "MOT-1A_1A") (pintype "power_in"))
    )
    (net (code "93") (name "Net-(P4-MOT-1B)") (class "Default")
      (node (ref "JP13") (pin "4") (pinfunction "4_4") (pintype "passive"))
      (node (ref "P4") (pin "1B") (pinfunction "MOT-1B_1B") (pintype "power_in"))
    )
    (net (code "94") (name "Net-(P4-MOT-2A)") (class "Default")
      (node (ref "JP13") (pin "2") (pinfunction "2_2") (pintype "passive"))
      (node (ref "P4") (pin "2A") (pinfunction "MOT-2A_2A") (pintype "power_in"))
    )
    (net (code "95") (name "Net-(P4-MOT-2B)") (class "Default")
      (node (ref "JP13") (pin "1") (pinfunction "1_1") (pintype "passive"))
      (node (ref "P4") (pin "2B") (pinfunction "MOT-2B_2B") (pintype "power_in"))
    )
    (net (code "96") (name "Net-(P4-PadMS1)") (class "Default")
      (node (ref "P4") (pin "MS1") (pinfunction "MS1_MS1") (pintype "input"))
      (node (ref "SJ12") (pin "1") (pinfunction "1_1") (pintype "passive"))
    )
    (net (code "97") (name "Net-(P4-PadMS2)") (class "Default")
      (node (ref "P4") (pin "MS2") (pinfunction "MS2_MS2") (pintype "input"))
      (node (ref "SJ8") (pin "1") (pinfunction "1_1") (pintype "passive"))
    )
    (net (code "98") (name "Net-(P4-PadMS3)") (class "Default")
      (node (ref "P4") (pin "MS3") (pinfunction "MS3_MS3") (pintype "input"))
      (node (ref "SJ4") (pin "1") (pinfunction "1_1") (pintype "passive"))
    )
    (net (code "99") (name "Net-(P4-~{RESET})") (class "Default")
      (node (ref "P4") (pin "!RST") (pinfunction "~{RESET}_!RST") (pintype "input"))
      (node (ref "P4") (pin "!SLP") (pinfunction "~{SLEEP}_!SLP") (pintype "input"))
    )
    (net (code "100") (name "Net-(Q1-D)") (class "Default")
      (node (ref "D1") (pin "C") (pinfunction "C_C") (pintype "passive"))
      (node (ref "F2") (pin "P$1") (pinfunction "P$1_P$1") (pintype "passive"))
      (node (ref "Q1") (pin "3") (pinfunction "D_3") (pintype "passive"))
    )
    (net (code "101") (name "Net-(Q1-G)") (class "Default")
      (node (ref "Q1") (pin "1") (pinfunction "G_1") (pintype "passive"))
      (node (ref "R3") (pin "2") (pinfunction "2_2") (pintype "passive"))
    )
    (net (code "102") (name "Net-(Q2-D)") (class "Default")
      (node (ref "J5") (pin "1") (pinfunction "1_1") (pintype "power_in"))
      (node (ref "J5") (pin "2") (pinfunction "2_2") (pintype "power_in"))
      (node (ref "Q2") (pin "5-8") (pinfunction "D_5-8") (pintype "passive"))
    )
    (net (code "103") (name "Net-(Q2-G)") (class "Default")
      (node (ref "Q2") (pin "4") (pinfunction "G_4") (pintype "passive"))
      (node (ref "R7") (pin "2") (pinfunction "2_2") (pintype "passive"))
    )
    (net (code "104") (name "Net-(Q3-D)") (class "Default")
      (node (ref "J7") (pin "1") (pinfunction "1_1") (pintype "power_in"))
      (node (ref "J7") (pin "2") (pinfunction "2_2") (pintype "power_in"))
      (node (ref "Q3") (pin "5-8") (pinfunction "D_5-8") (pintype "passive"))
    )
    (net (code "105") (name "Net-(Q3-G)") (class "Default")
      (node (ref "Q3") (pin "4") (pinfunction "G_4") (pintype "passive"))
      (node (ref "R16") (pin "2") (pinfunction "2_2") (pintype "passive"))
    )
    (net (code "106") (name "Net-(Q4-B)") (class "Default")
      (node (ref "JP7") (pin "1") (pinfunction "1_1") (pintype "passive"))
      (node (ref "Q4") (pin "1") (pinfunction "B_1") (pintype "passive"))
    )
    (net (code "107") (name "Net-(U1-OUT)") (class "Default")
      (node (ref "R7") (pin "1") (pinfunction "1_1") (pintype "passive"))
      (node (ref "U1") (pin "5") (pinfunction "OUT_5") (pintype "passive"))
    )
    (net (code "108") (name "Net-(U2-CB)") (class "Default")
      (node (ref "C28") (pin "2") (pinfunction "2_2") (pintype "passive"))
      (node (ref "U2") (pin "1") (pinfunction "CB_1") (pintype "passive"))
    )
    (net (code "109") (name "Net-(U2-FB)") (class "Default")
      (node (ref "R13") (pin "2") (pinfunction "2_2") (pintype "passive"))
      (node (ref "R14") (pin "1") (pinfunction "1_1") (pintype "passive"))
      (node (ref "U2") (pin "3") (pinfunction "FB_3") (pintype "passive"))
    )
    (net (code "110") (name "Net-(U2-SW)") (class "Default")
      (node (ref "C28") (pin "1") (pinfunction "1_1") (pintype "passive"))
      (node (ref "D2") (pin "C") (pinfunction "C_C") (pintype "passive"))
      (node (ref "L5") (pin "1") (pinfunction "1_1") (pintype "passive"))
      (node (ref "U2") (pin "6") (pinfunction "SW_6") (pintype "passive"))
    )
    (net (code "111") (name "Net-(U2-~{SHDN})") (class "Default")
      (node (ref "R5") (pin "2") (pinfunction "2_2") (pintype "passive"))
      (node (ref "R6") (pin "1") (pinfunction "1_1") (pintype "passive"))
      (node (ref "U2") (pin "4") (pinfunction "~{SHDN}_4") (pintype "input"))
    )
    (net (code "112") (name "Net-(U3-OUT)") (class "Default")
      (node (ref "R16") (pin "1") (pinfunction "1_1") (pintype "passive"))
      (node (ref "U3") (pin "5") (pinfunction "OUT_5") (pintype "passive"))
    )
    (net (code "113") (name "Net-(U5C-DFSDM)") (class "Default")
      (node (ref "R10") (pin "2") (pinfunction "2_2") (pintype "passive"))
      (node (ref "U5") (pin "32") (pinfunction "DFSDM_32") (pintype "input"))
    )
    (net (code "114") (name "Net-(U5C-DFSDP)") (class "Default")
      (node (ref "R11") (pin "2") (pinfunction "2_2") (pintype "passive"))
      (node (ref "U5") (pin "31") (pinfunction "DFSDP_31") (pintype "input"))
    )
    (net (code "115") (name "Net-(U5C-FWUP)") (class "Default")
      (node (ref "R9") (pin "1") (pinfunction "1_1") (pintype "passive"))
      (node (ref "U5") (pin "40") (pinfunction "FWUP_40") (pintype "input"))
    )
    (net (code "116") (name "Net-(U5C-TST)") (class "Default")
      (node (ref "R12") (pin "1") (pinfunction "1_1") (pintype "passive"))
      (node (ref "U5") (pin "38") (pinfunction "TST_38") (pintype "input"))
    )
    (net (code "117") (name "Net-(U5C-VBG)") (class "Default")
      (node (ref "C27") (pin "1") (pinfunction "1_1") (pintype "passive"))
      (node (ref "R8") (pin "2") (pinfunction "2_2") (pintype "passive"))
      (node (ref "U5") (pin "29") (pinfunction "VBG_29") (pintype "passive"))
    )
    (net (code "118") (name "VDD") (class "Default")
      (node (ref "C12") (pin "1") (pinfunction "1_1") (pintype "passive"))
      (node (ref "C14") (pin "1") (pinfunction "1_1") (pintype "passive"))
      (node (ref "C18") (pin "1") (pinfunction "1_1") (pintype "passive"))
      (node (ref "C2") (pin "1") (pinfunction "1_1") (pintype "passive"))
      (node (ref "C22") (pin "1") (pinfunction "1_1") (pintype "passive"))
      (node (ref "C4") (pin "1") (pinfunction "1_1") (pintype "passive"))
      (node (ref "C8") (pin "1") (pinfunction "1_1") (pintype "passive"))
      (node (ref "L2") (pin "1") (pinfunction "1_1") (pintype "passive"))
      (node (ref "U5") (pin "10") (pinfunction "VDDCORE1_10") (pintype "input"))
      (node (ref "U5") (pin "34") (pinfunction "VDDCORE2_34") (pintype "input"))
      (node (ref "U5") (pin "42") (pinfunction "VDDOUT_42") (pintype "output"))
      (node (ref "U5") (pin "45") (pinfunction "VDDCORE3_45") (pintype "input"))
      (node (ref "U5") (pin "71") (pinfunction "VDDCORE4_71") (pintype "input"))
      (node (ref "U5") (pin "89") (pinfunction "VDDCORE5_89") (pintype "input"))
    )
    (net (code "119") (name "unconnected-(J9-PadID)") (class "Default")
      (node (ref "J9") (pin "ID") (pinfunction "ID_ID") (pintype "bidirectional"))
    )
    (net (code "120") (name "unconnected-(JP4-Pad7)") (class "Default")
      (node (ref "JP4") (pin "7") (pinfunction "7_7") (pintype "passive"))
    )
    (net (code "121") (name "unconnected-(U5A-PA0{slash}CANTX0{slash}PWML3-Pad13)") (class "Default")
      (node (ref "U5") (pin "13") (pinfunction "PA0/CANTX0/PWML3_13") (pintype "bidirectional"))
    )
    (net (code "122") (name "unconnected-(U5A-PA16{slash}SPCK1{slash}TD{slash}AD7-Pad56)") (class "Default")
      (node (ref "U5") (pin "56") (pinfunction "PA16/SPCK1/TD/AD7_56") (pintype "bidirectional"))
    )
    (net (code "123") (name "unconnected-(U5B-PB0{slash}TIOA3-Pad80)") (class "Default")
      (node (ref "U5") (pin "80") (pinfunction "PB0/TIOA3_80") (pintype "bidirectional"))
    )
    (net (code "124") (name "unconnected-(U5B-PB1{slash}TIOB3-Pad81)") (class "Default")
      (node (ref "U5") (pin "81") (pinfunction "PB1/TIOB3_81") (pintype "bidirectional"))
    )
    (net (code "125") (name "unconnected-(U5B-PB2{slash}TIOA4-Pad82)") (class "Default")
      (node (ref "U5") (pin "82") (pinfunction "PB2/TIOA4_82") (pintype "bidirectional"))
    )
    (net (code "126") (name "unconnected-(U5B-PB3{slash}TIOB4-Pad83)") (class "Default")
      (node (ref "U5") (pin "83") (pinfunction "PB3/TIOB4_83") (pintype "bidirectional"))
    )
    (net (code "127") (name "unconnected-(U5B-PB4{slash}TIOA5-Pad84)") (class "Default")
      (node (ref "U5") (pin "84") (pinfunction "PB4/TIOA5_84") (pintype "bidirectional"))
    )
    (net (code "128") (name "unconnected-(U5B-PB6{slash}PWML4-Pad86)") (class "Default")
      (node (ref "U5") (pin "86") (pinfunction "PB6/PWML4_86") (pintype "bidirectional"))
    )
    (net (code "129") (name "unconnected-(U5B-PB7{slash}PWML5-Pad87)") (class "Default")
      (node (ref "U5") (pin "87") (pinfunction "PB7/PWML5_87") (pintype "bidirectional"))
    )
    (net (code "130") (name "unconnected-(U5B-PB8{slash}PWML6-Pad88)") (class "Default")
      (node (ref "U5") (pin "88") (pinfunction "PB8/PWML6_88") (pintype "bidirectional"))
    )
    (net (code "131") (name "unconnected-(U5B-PB9{slash}PWML7-Pad92)") (class "Default")
      (node (ref "U5") (pin "92") (pinfunction "PB9/PWML7_92") (pintype "bidirectional"))
    )
    (net (code "132") (name "unconnected-(U5B-PB10{slash}UOTGVBOF{slash}A18-Pad93)") (class "Default")
      (node (ref "U5") (pin "93") (pinfunction "PB10/UOTGVBOF/A18_93") (pintype "bidirectional"))
    )
    (net (code "133") (name "unconnected-(U5B-PB11{slash}UOTGID{slash}A19-Pad94)") (class "Default")
      (node (ref "U5") (pin "94") (pinfunction "PB11/UOTGID/A19_94") (pintype "bidirectional"))
    )
    (net (code "134") (name "unconnected-(U5B-PB27{slash}NCS3{slash}TIOB0-Pad46)") (class "Default")
      (node (ref "U5") (pin "46") (pinfunction "PB27/NCS3/TIOB0_46") (pintype "bidirectional"))
    )
    (net (code "135") (name "unconnected-(U5C-XIN32-Pad36)") (class "Default")
      (node (ref "U5") (pin "36") (pinfunction "XIN32_36") (pintype "output"))
    )
    (net (code "136") (name "unconnected-(U5C-XOUT32-Pad37)") (class "Default")
      (node (ref "U5") (pin "37") (pinfunction "XOUT32_37") (pintype "output"))
    )
  )
)
